# ASIC_2.net
KiCad netlist of a schematic drawn in Altium Designer
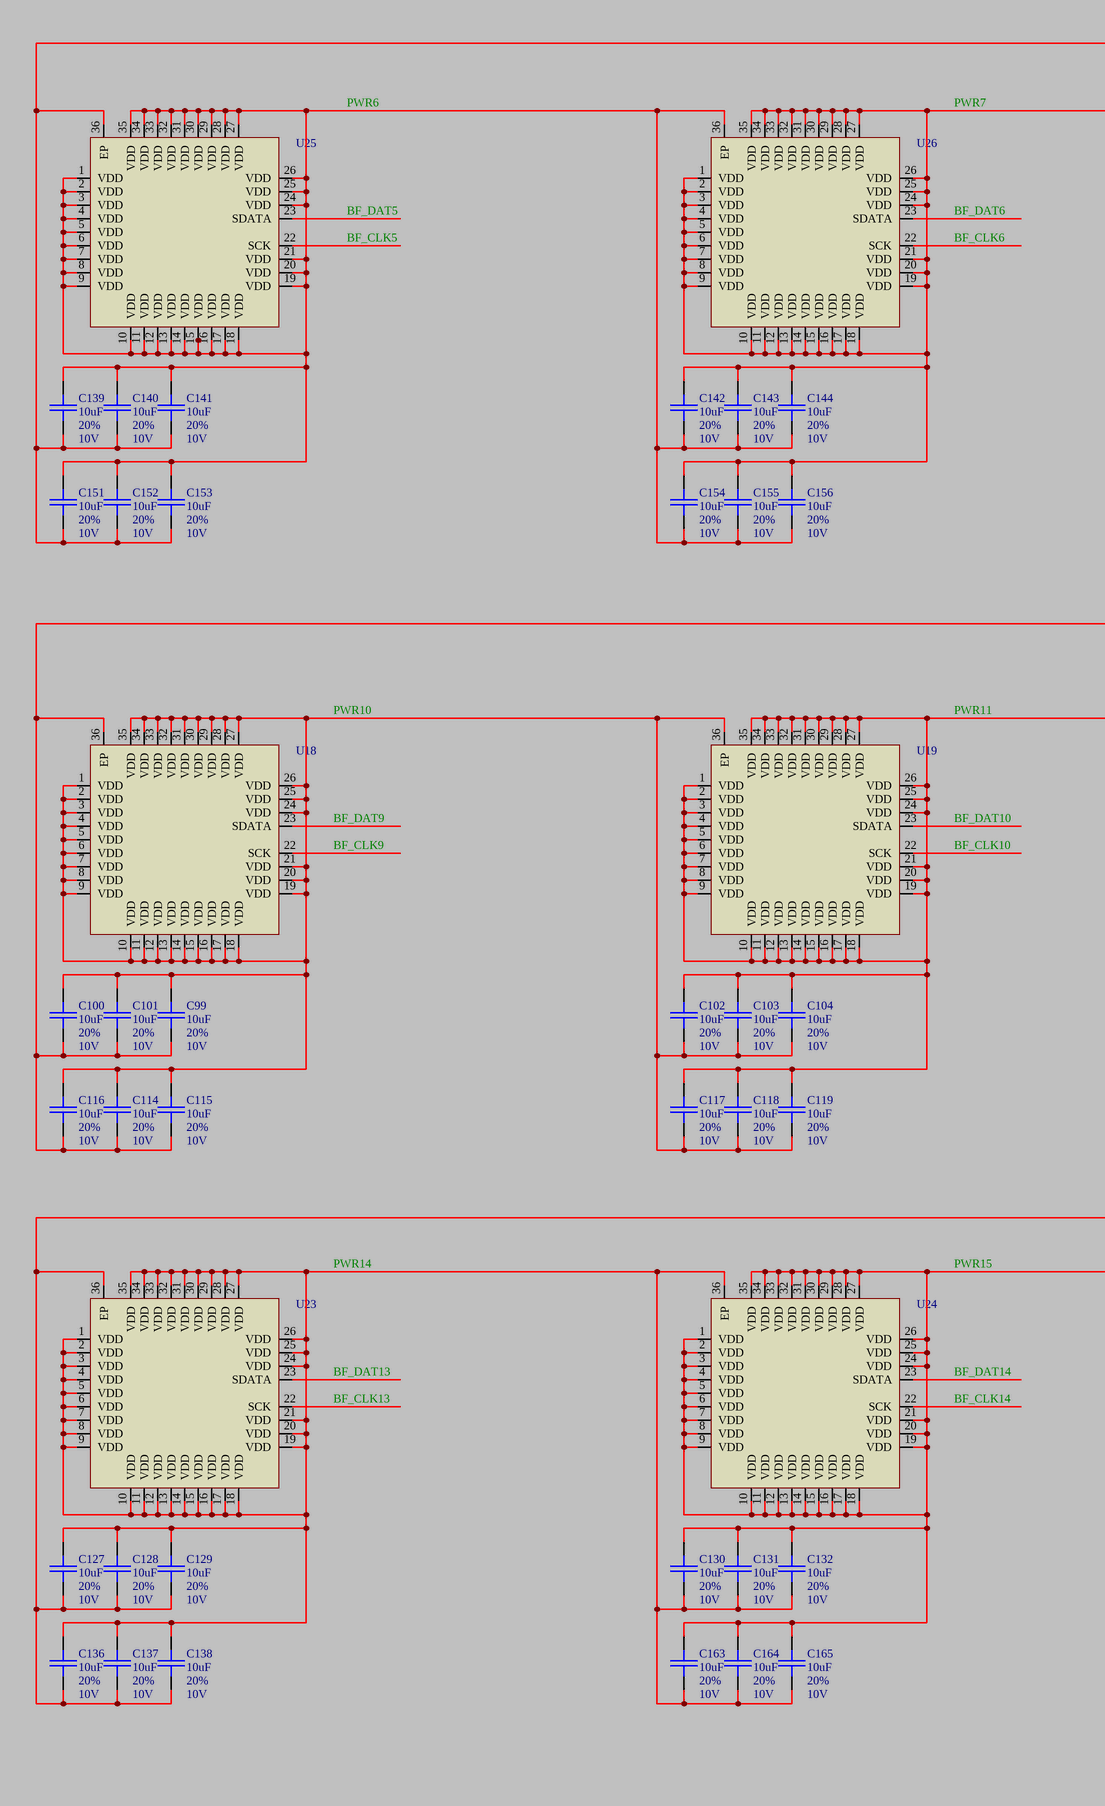
[diagram p0: ASIC_2.SchDoc, left]
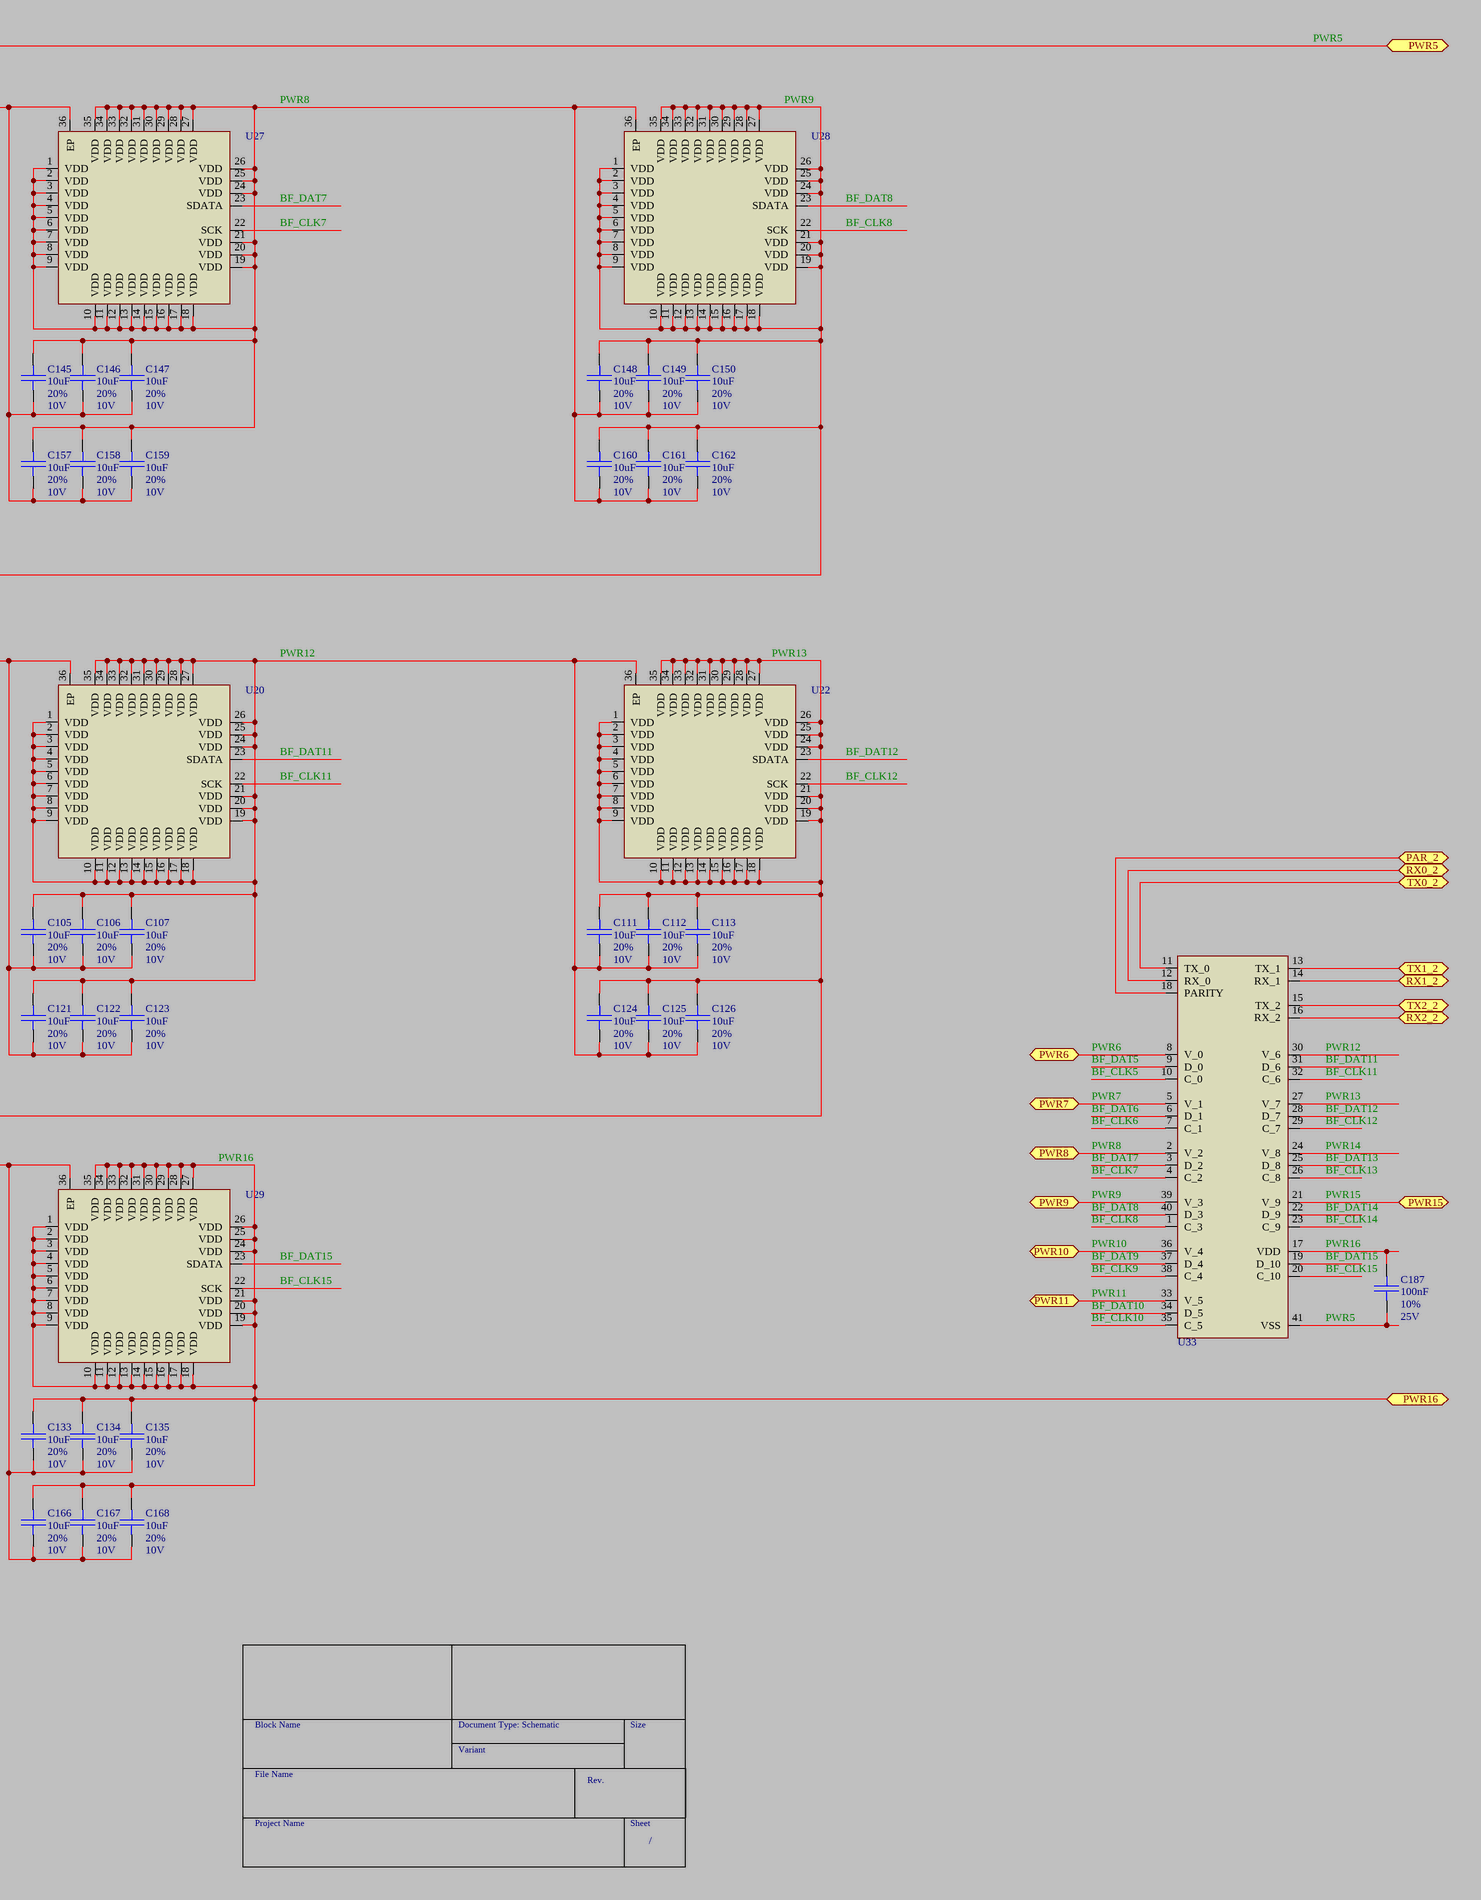
[diagram p1: ASIC_2.SchDoc, right]

(export (version "E")
  (design (tool "Eeschema 10.0.6"))
  (components
    (comp (ref "C99")
      (value "C")
      (footprint "SMD_0402_CAPC1005X70N")
      (fields
        (field (name "DB_PART_NUMBER") "CAP000047481")
        (field (name "DB_VALUE") "10uF")
        (field (name "DB_TOLERANCE") "20%")
        (field (name "DB_VOLTAGE") "10V")
        (field (name "DB_MANUFACTURER_PART") "SAMSUNG    CL05A106MP5NUNC")
        (field (name "DB_APPROVED_BY") "VSN")
      )
      (libsource (lib "Database_Libs1") (part "C"))
    )
    (comp (ref "C100")
      (value "C")
      (footprint "SMD_0402_CAPC1005X70N")
      (fields
        (field (name "DB_PART_NUMBER") "CAP000047481")
        (field (name "DB_VALUE") "10uF")
        (field (name "DB_TOLERANCE") "20%")
        (field (name "DB_VOLTAGE") "10V")
        (field (name "DB_MANUFACTURER_PART") "SAMSUNG    CL05A106MP5NUNC")
        (field (name "DB_APPROVED_BY") "VSN")
      )
      (libsource (lib "Database_Libs1") (part "C"))
    )
    (comp (ref "C101")
      (value "C")
      (footprint "SMD_0402_CAPC1005X70N")
      (fields
        (field (name "DB_PART_NUMBER") "CAP000047481")
        (field (name "DB_VALUE") "10uF")
        (field (name "DB_TOLERANCE") "20%")
        (field (name "DB_VOLTAGE") "10V")
        (field (name "DB_MANUFACTURER_PART") "SAMSUNG    CL05A106MP5NUNC")
        (field (name "DB_APPROVED_BY") "VSN")
      )
      (libsource (lib "Database_Libs1") (part "C"))
    )
    (comp (ref "C102")
      (value "C")
      (footprint "SMD_0402_CAPC1005X70N")
      (fields
        (field (name "DB_PART_NUMBER") "CAP000047481")
        (field (name "DB_VALUE") "10uF")
        (field (name "DB_TOLERANCE") "20%")
        (field (name "DB_VOLTAGE") "10V")
        (field (name "DB_MANUFACTURER_PART") "SAMSUNG    CL05A106MP5NUNC")
        (field (name "DB_APPROVED_BY") "VSN")
      )
      (libsource (lib "Database_Libs1") (part "C"))
    )
    (comp (ref "C103")
      (value "C")
      (footprint "SMD_0402_CAPC1005X70N")
      (fields
        (field (name "DB_PART_NUMBER") "CAP000047481")
        (field (name "DB_VALUE") "10uF")
        (field (name "DB_TOLERANCE") "20%")
        (field (name "DB_VOLTAGE") "10V")
        (field (name "DB_MANUFACTURER_PART") "SAMSUNG    CL05A106MP5NUNC")
        (field (name "DB_APPROVED_BY") "VSN")
      )
      (libsource (lib "Database_Libs1") (part "C"))
    )
    (comp (ref "C104")
      (value "C")
      (footprint "SMD_0402_CAPC1005X70N")
      (fields
        (field (name "DB_PART_NUMBER") "CAP000047481")
        (field (name "DB_VALUE") "10uF")
        (field (name "DB_TOLERANCE") "20%")
        (field (name "DB_VOLTAGE") "10V")
        (field (name "DB_MANUFACTURER_PART") "SAMSUNG    CL05A106MP5NUNC")
        (field (name "DB_APPROVED_BY") "VSN")
      )
      (libsource (lib "Database_Libs1") (part "C"))
    )
    (comp (ref "C105")
      (value "C")
      (footprint "SMD_0402_CAPC1005X70N")
      (fields
        (field (name "DB_PART_NUMBER") "CAP000047481")
        (field (name "DB_VALUE") "10uF")
        (field (name "DB_TOLERANCE") "20%")
        (field (name "DB_VOLTAGE") "10V")
        (field (name "DB_MANUFACTURER_PART") "SAMSUNG    CL05A106MP5NUNC")
        (field (name "DB_APPROVED_BY") "VSN")
      )
      (libsource (lib "Database_Libs1") (part "C"))
    )
    (comp (ref "C106")
      (value "C")
      (footprint "SMD_0402_CAPC1005X70N")
      (fields
        (field (name "DB_PART_NUMBER") "CAP000047481")
        (field (name "DB_VALUE") "10uF")
        (field (name "DB_TOLERANCE") "20%")
        (field (name "DB_VOLTAGE") "10V")
        (field (name "DB_MANUFACTURER_PART") "SAMSUNG    CL05A106MP5NUNC")
        (field (name "DB_APPROVED_BY") "VSN")
      )
      (libsource (lib "Database_Libs1") (part "C"))
    )
    (comp (ref "C107")
      (value "C")
      (footprint "SMD_0402_CAPC1005X70N")
      (fields
        (field (name "DB_PART_NUMBER") "CAP000047481")
        (field (name "DB_VALUE") "10uF")
        (field (name "DB_TOLERANCE") "20%")
        (field (name "DB_VOLTAGE") "10V")
        (field (name "DB_MANUFACTURER_PART") "SAMSUNG    CL05A106MP5NUNC")
        (field (name "DB_APPROVED_BY") "VSN")
      )
      (libsource (lib "Database_Libs1") (part "C"))
    )
    (comp (ref "C111")
      (value "C")
      (footprint "SMD_0402_CAPC1005X70N")
      (fields
        (field (name "DB_PART_NUMBER") "CAP000047481")
        (field (name "DB_VALUE") "10uF")
        (field (name "DB_TOLERANCE") "20%")
        (field (name "DB_VOLTAGE") "10V")
        (field (name "DB_MANUFACTURER_PART") "SAMSUNG    CL05A106MP5NUNC")
        (field (name "DB_APPROVED_BY") "VSN")
      )
      (libsource (lib "Database_Libs1") (part "C"))
    )
    (comp (ref "C112")
      (value "C")
      (footprint "SMD_0402_CAPC1005X70N")
      (fields
        (field (name "DB_PART_NUMBER") "CAP000047481")
        (field (name "DB_VALUE") "10uF")
        (field (name "DB_TOLERANCE") "20%")
        (field (name "DB_VOLTAGE") "10V")
        (field (name "DB_MANUFACTURER_PART") "SAMSUNG    CL05A106MP5NUNC")
        (field (name "DB_APPROVED_BY") "VSN")
      )
      (libsource (lib "Database_Libs1") (part "C"))
    )
    (comp (ref "C113")
      (value "C")
      (footprint "SMD_0402_CAPC1005X70N")
      (fields
        (field (name "DB_PART_NUMBER") "CAP000047481")
        (field (name "DB_VALUE") "10uF")
        (field (name "DB_TOLERANCE") "20%")
        (field (name "DB_VOLTAGE") "10V")
        (field (name "DB_MANUFACTURER_PART") "SAMSUNG    CL05A106MP5NUNC")
        (field (name "DB_APPROVED_BY") "VSN")
      )
      (libsource (lib "Database_Libs1") (part "C"))
    )
    (comp (ref "C114")
      (value "C")
      (footprint "SMD_0402_CAPC1005X70N")
      (fields
        (field (name "DB_PART_NUMBER") "CAP000047481")
        (field (name "DB_VALUE") "10uF")
        (field (name "DB_TOLERANCE") "20%")
        (field (name "DB_VOLTAGE") "10V")
        (field (name "DB_MANUFACTURER_PART") "SAMSUNG    CL05A106MP5NUNC")
        (field (name "DB_APPROVED_BY") "VSN")
      )
      (libsource (lib "Database_Libs1") (part "C"))
    )
    (comp (ref "C115")
      (value "C")
      (footprint "SMD_0402_CAPC1005X70N")
      (fields
        (field (name "DB_PART_NUMBER") "CAP000047481")
        (field (name "DB_VALUE") "10uF")
        (field (name "DB_TOLERANCE") "20%")
        (field (name "DB_VOLTAGE") "10V")
        (field (name "DB_MANUFACTURER_PART") "SAMSUNG    CL05A106MP5NUNC")
        (field (name "DB_APPROVED_BY") "VSN")
      )
      (libsource (lib "Database_Libs1") (part "C"))
    )
    (comp (ref "C116")
      (value "C")
      (footprint "SMD_0402_CAPC1005X70N")
      (fields
        (field (name "DB_PART_NUMBER") "CAP000047481")
        (field (name "DB_VALUE") "10uF")
        (field (name "DB_TOLERANCE") "20%")
        (field (name "DB_VOLTAGE") "10V")
        (field (name "DB_MANUFACTURER_PART") "SAMSUNG    CL05A106MP5NUNC")
        (field (name "DB_APPROVED_BY") "VSN")
      )
      (libsource (lib "Database_Libs1") (part "C"))
    )
    (comp (ref "C117")
      (value "C")
      (footprint "SMD_0402_CAPC1005X70N")
      (fields
        (field (name "DB_PART_NUMBER") "CAP000047481")
        (field (name "DB_VALUE") "10uF")
        (field (name "DB_TOLERANCE") "20%")
        (field (name "DB_VOLTAGE") "10V")
        (field (name "DB_MANUFACTURER_PART") "SAMSUNG    CL05A106MP5NUNC")
        (field (name "DB_APPROVED_BY") "VSN")
      )
      (libsource (lib "Database_Libs1") (part "C"))
    )
    (comp (ref "C118")
      (value "C")
      (footprint "SMD_0402_CAPC1005X70N")
      (fields
        (field (name "DB_PART_NUMBER") "CAP000047481")
        (field (name "DB_VALUE") "10uF")
        (field (name "DB_TOLERANCE") "20%")
        (field (name "DB_VOLTAGE") "10V")
        (field (name "DB_MANUFACTURER_PART") "SAMSUNG    CL05A106MP5NUNC")
        (field (name "DB_APPROVED_BY") "VSN")
      )
      (libsource (lib "Database_Libs1") (part "C"))
    )
    (comp (ref "C119")
      (value "C")
      (footprint "SMD_0402_CAPC1005X70N")
      (fields
        (field (name "DB_PART_NUMBER") "CAP000047481")
        (field (name "DB_VALUE") "10uF")
        (field (name "DB_TOLERANCE") "20%")
        (field (name "DB_VOLTAGE") "10V")
        (field (name "DB_MANUFACTURER_PART") "SAMSUNG    CL05A106MP5NUNC")
        (field (name "DB_APPROVED_BY") "VSN")
      )
      (libsource (lib "Database_Libs1") (part "C"))
    )
    (comp (ref "C121")
      (value "C")
      (footprint "SMD_0402_CAPC1005X70N")
      (fields
        (field (name "DB_PART_NUMBER") "CAP000047481")
        (field (name "DB_VALUE") "10uF")
        (field (name "DB_TOLERANCE") "20%")
        (field (name "DB_VOLTAGE") "10V")
        (field (name "DB_MANUFACTURER_PART") "SAMSUNG    CL05A106MP5NUNC")
        (field (name "DB_APPROVED_BY") "VSN")
      )
      (libsource (lib "Database_Libs1") (part "C"))
    )
    (comp (ref "C122")
      (value "C")
      (footprint "SMD_0402_CAPC1005X70N")
      (fields
        (field (name "DB_PART_NUMBER") "CAP000047481")
        (field (name "DB_VALUE") "10uF")
        (field (name "DB_TOLERANCE") "20%")
        (field (name "DB_VOLTAGE") "10V")
        (field (name "DB_MANUFACTURER_PART") "SAMSUNG    CL05A106MP5NUNC")
        (field (name "DB_APPROVED_BY") "VSN")
      )
      (libsource (lib "Database_Libs1") (part "C"))
    )
    (comp (ref "C123")
      (value "C")
      (footprint "SMD_0402_CAPC1005X70N")
      (fields
        (field (name "DB_PART_NUMBER") "CAP000047481")
        (field (name "DB_VALUE") "10uF")
        (field (name "DB_TOLERANCE") "20%")
        (field (name "DB_VOLTAGE") "10V")
        (field (name "DB_MANUFACTURER_PART") "SAMSUNG    CL05A106MP5NUNC")
        (field (name "DB_APPROVED_BY") "VSN")
      )
      (libsource (lib "Database_Libs1") (part "C"))
    )
    (comp (ref "C124")
      (value "C")
      (footprint "SMD_0402_CAPC1005X70N")
      (fields
        (field (name "DB_PART_NUMBER") "CAP000047481")
        (field (name "DB_VALUE") "10uF")
        (field (name "DB_TOLERANCE") "20%")
        (field (name "DB_VOLTAGE") "10V")
        (field (name "DB_MANUFACTURER_PART") "SAMSUNG    CL05A106MP5NUNC")
        (field (name "DB_APPROVED_BY") "VSN")
      )
      (libsource (lib "Database_Libs1") (part "C"))
    )
    (comp (ref "C125")
      (value "C")
      (footprint "SMD_0402_CAPC1005X70N")
      (fields
        (field (name "DB_PART_NUMBER") "CAP000047481")
        (field (name "DB_VALUE") "10uF")
        (field (name "DB_TOLERANCE") "20%")
        (field (name "DB_VOLTAGE") "10V")
        (field (name "DB_MANUFACTURER_PART") "SAMSUNG    CL05A106MP5NUNC")
        (field (name "DB_APPROVED_BY") "VSN")
      )
      (libsource (lib "Database_Libs1") (part "C"))
    )
    (comp (ref "C126")
      (value "C")
      (footprint "SMD_0402_CAPC1005X70N")
      (fields
        (field (name "DB_PART_NUMBER") "CAP000047481")
        (field (name "DB_VALUE") "10uF")
        (field (name "DB_TOLERANCE") "20%")
        (field (name "DB_VOLTAGE") "10V")
        (field (name "DB_MANUFACTURER_PART") "SAMSUNG    CL05A106MP5NUNC")
        (field (name "DB_APPROVED_BY") "VSN")
      )
      (libsource (lib "Database_Libs1") (part "C"))
    )
    (comp (ref "C127")
      (value "C")
      (footprint "SMD_0402_CAPC1005X70N")
      (fields
        (field (name "DB_PART_NUMBER") "CAP000047481")
        (field (name "DB_VALUE") "10uF")
        (field (name "DB_TOLERANCE") "20%")
        (field (name "DB_VOLTAGE") "10V")
        (field (name "DB_MANUFACTURER_PART") "SAMSUNG    CL05A106MP5NUNC")
        (field (name "DB_APPROVED_BY") "VSN")
      )
      (libsource (lib "Database_Libs1") (part "C"))
    )
    (comp (ref "C128")
      (value "C")
      (footprint "SMD_0402_CAPC1005X70N")
      (fields
        (field (name "DB_PART_NUMBER") "CAP000047481")
        (field (name "DB_VALUE") "10uF")
        (field (name "DB_TOLERANCE") "20%")
        (field (name "DB_VOLTAGE") "10V")
        (field (name "DB_MANUFACTURER_PART") "SAMSUNG    CL05A106MP5NUNC")
        (field (name "DB_APPROVED_BY") "VSN")
      )
      (libsource (lib "Database_Libs1") (part "C"))
    )
    (comp (ref "C129")
      (value "C")
      (footprint "SMD_0402_CAPC1005X70N")
      (fields
        (field (name "DB_PART_NUMBER") "CAP000047481")
        (field (name "DB_VALUE") "10uF")
        (field (name "DB_TOLERANCE") "20%")
        (field (name "DB_VOLTAGE") "10V")
        (field (name "DB_MANUFACTURER_PART") "SAMSUNG    CL05A106MP5NUNC")
        (field (name "DB_APPROVED_BY") "VSN")
      )
      (libsource (lib "Database_Libs1") (part "C"))
    )
    (comp (ref "C130")
      (value "C")
      (footprint "SMD_0402_CAPC1005X70N")
      (fields
        (field (name "DB_PART_NUMBER") "CAP000047481")
        (field (name "DB_VALUE") "10uF")
        (field (name "DB_TOLERANCE") "20%")
        (field (name "DB_VOLTAGE") "10V")
        (field (name "DB_MANUFACTURER_PART") "SAMSUNG    CL05A106MP5NUNC")
        (field (name "DB_APPROVED_BY") "VSN")
      )
      (libsource (lib "Database_Libs1") (part "C"))
    )
    (comp (ref "C131")
      (value "C")
      (footprint "SMD_0402_CAPC1005X70N")
      (fields
        (field (name "DB_PART_NUMBER") "CAP000047481")
        (field (name "DB_VALUE") "10uF")
        (field (name "DB_TOLERANCE") "20%")
        (field (name "DB_VOLTAGE") "10V")
        (field (name "DB_MANUFACTURER_PART") "SAMSUNG    CL05A106MP5NUNC")
        (field (name "DB_APPROVED_BY") "VSN")
      )
      (libsource (lib "Database_Libs1") (part "C"))
    )
    (comp (ref "C132")
      (value "C")
      (footprint "SMD_0402_CAPC1005X70N")
      (fields
        (field (name "DB_PART_NUMBER") "CAP000047481")
        (field (name "DB_VALUE") "10uF")
        (field (name "DB_TOLERANCE") "20%")
        (field (name "DB_VOLTAGE") "10V")
        (field (name "DB_MANUFACTURER_PART") "SAMSUNG    CL05A106MP5NUNC")
        (field (name "DB_APPROVED_BY") "VSN")
      )
      (libsource (lib "Database_Libs1") (part "C"))
    )
    (comp (ref "C133")
      (value "C")
      (footprint "SMD_0402_CAPC1005X70N")
      (fields
        (field (name "DB_PART_NUMBER") "CAP000047481")
        (field (name "DB_VALUE") "10uF")
        (field (name "DB_TOLERANCE") "20%")
        (field (name "DB_VOLTAGE") "10V")
        (field (name "DB_MANUFACTURER_PART") "SAMSUNG    CL05A106MP5NUNC")
        (field (name "DB_APPROVED_BY") "VSN")
      )
      (libsource (lib "Database_Libs1") (part "C"))
    )
    (comp (ref "C134")
      (value "C")
      (footprint "SMD_0402_CAPC1005X70N")
      (fields
        (field (name "DB_PART_NUMBER") "CAP000047481")
        (field (name "DB_VALUE") "10uF")
        (field (name "DB_TOLERANCE") "20%")
        (field (name "DB_VOLTAGE") "10V")
        (field (name "DB_MANUFACTURER_PART") "SAMSUNG    CL05A106MP5NUNC")
        (field (name "DB_APPROVED_BY") "VSN")
      )
      (libsource (lib "Database_Libs1") (part "C"))
    )
    (comp (ref "C135")
      (value "C")
      (footprint "SMD_0402_CAPC1005X70N")
      (fields
        (field (name "DB_PART_NUMBER") "CAP000047481")
        (field (name "DB_VALUE") "10uF")
        (field (name "DB_TOLERANCE") "20%")
        (field (name "DB_VOLTAGE") "10V")
        (field (name "DB_MANUFACTURER_PART") "SAMSUNG    CL05A106MP5NUNC")
        (field (name "DB_APPROVED_BY") "VSN")
      )
      (libsource (lib "Database_Libs1") (part "C"))
    )
    (comp (ref "C136")
      (value "C")
      (footprint "SMD_0402_CAPC1005X70N")
      (fields
        (field (name "DB_PART_NUMBER") "CAP000047481")
        (field (name "DB_VALUE") "10uF")
        (field (name "DB_TOLERANCE") "20%")
        (field (name "DB_VOLTAGE") "10V")
        (field (name "DB_MANUFACTURER_PART") "SAMSUNG    CL05A106MP5NUNC")
        (field (name "DB_APPROVED_BY") "VSN")
      )
      (libsource (lib "Database_Libs1") (part "C"))
    )
    (comp (ref "C137")
      (value "C")
      (footprint "SMD_0402_CAPC1005X70N")
      (fields
        (field (name "DB_PART_NUMBER") "CAP000047481")
        (field (name "DB_VALUE") "10uF")
        (field (name "DB_TOLERANCE") "20%")
        (field (name "DB_VOLTAGE") "10V")
        (field (name "DB_MANUFACTURER_PART") "SAMSUNG    CL05A106MP5NUNC")
        (field (name "DB_APPROVED_BY") "VSN")
      )
      (libsource (lib "Database_Libs1") (part "C"))
    )
    (comp (ref "C138")
      (value "C")
      (footprint "SMD_0402_CAPC1005X70N")
      (fields
        (field (name "DB_PART_NUMBER") "CAP000047481")
        (field (name "DB_VALUE") "10uF")
        (field (name "DB_TOLERANCE") "20%")
        (field (name "DB_VOLTAGE") "10V")
        (field (name "DB_MANUFACTURER_PART") "SAMSUNG    CL05A106MP5NUNC")
        (field (name "DB_APPROVED_BY") "VSN")
      )
      (libsource (lib "Database_Libs1") (part "C"))
    )
    (comp (ref "C139")
      (value "C")
      (footprint "SMD_0402_CAPC1005X70N")
      (fields
        (field (name "DB_PART_NUMBER") "CAP000047481")
        (field (name "DB_VALUE") "10uF")
        (field (name "DB_TOLERANCE") "20%")
        (field (name "DB_VOLTAGE") "10V")
        (field (name "DB_MANUFACTURER_PART") "SAMSUNG    CL05A106MP5NUNC")
        (field (name "DB_APPROVED_BY") "VSN")
      )
      (libsource (lib "Database_Libs1") (part "C"))
    )
    (comp (ref "C140")
      (value "C")
      (footprint "SMD_0402_CAPC1005X70N")
      (fields
        (field (name "DB_PART_NUMBER") "CAP000047481")
        (field (name "DB_VALUE") "10uF")
        (field (name "DB_TOLERANCE") "20%")
        (field (name "DB_VOLTAGE") "10V")
        (field (name "DB_MANUFACTURER_PART") "SAMSUNG    CL05A106MP5NUNC")
        (field (name "DB_APPROVED_BY") "VSN")
      )
      (libsource (lib "Database_Libs1") (part "C"))
    )
    (comp (ref "C141")
      (value "C")
      (footprint "SMD_0402_CAPC1005X70N")
      (fields
        (field (name "DB_PART_NUMBER") "CAP000047481")
        (field (name "DB_VALUE") "10uF")
        (field (name "DB_TOLERANCE") "20%")
        (field (name "DB_VOLTAGE") "10V")
        (field (name "DB_MANUFACTURER_PART") "SAMSUNG    CL05A106MP5NUNC")
        (field (name "DB_APPROVED_BY") "VSN")
      )
      (libsource (lib "Database_Libs1") (part "C"))
    )
    (comp (ref "C142")
      (value "C")
      (footprint "SMD_0402_CAPC1005X70N")
      (fields
        (field (name "DB_PART_NUMBER") "CAP000047481")
        (field (name "DB_VALUE") "10uF")
        (field (name "DB_TOLERANCE") "20%")
        (field (name "DB_VOLTAGE") "10V")
        (field (name "DB_MANUFACTURER_PART") "SAMSUNG    CL05A106MP5NUNC")
        (field (name "DB_APPROVED_BY") "VSN")
      )
      (libsource (lib "Database_Libs1") (part "C"))
    )
    (comp (ref "C143")
      (value "C")
      (footprint "SMD_0402_CAPC1005X70N")
      (fields
        (field (name "DB_PART_NUMBER") "CAP000047481")
        (field (name "DB_VALUE") "10uF")
        (field (name "DB_TOLERANCE") "20%")
        (field (name "DB_VOLTAGE") "10V")
        (field (name "DB_MANUFACTURER_PART") "SAMSUNG    CL05A106MP5NUNC")
        (field (name "DB_APPROVED_BY") "VSN")
      )
      (libsource (lib "Database_Libs1") (part "C"))
    )
    (comp (ref "C144")
      (value "C")
      (footprint "SMD_0402_CAPC1005X70N")
      (fields
        (field (name "DB_PART_NUMBER") "CAP000047481")
        (field (name "DB_VALUE") "10uF")
        (field (name "DB_TOLERANCE") "20%")
        (field (name "DB_VOLTAGE") "10V")
        (field (name "DB_MANUFACTURER_PART") "SAMSUNG    CL05A106MP5NUNC")
        (field (name "DB_APPROVED_BY") "VSN")
      )
      (libsource (lib "Database_Libs1") (part "C"))
    )
    (comp (ref "C145")
      (value "C")
      (footprint "SMD_0402_CAPC1005X70N")
      (fields
        (field (name "DB_PART_NUMBER") "CAP000047481")
        (field (name "DB_VALUE") "10uF")
        (field (name "DB_TOLERANCE") "20%")
        (field (name "DB_VOLTAGE") "10V")
        (field (name "DB_MANUFACTURER_PART") "SAMSUNG    CL05A106MP5NUNC")
        (field (name "DB_APPROVED_BY") "VSN")
      )
      (libsource (lib "Database_Libs1") (part "C"))
    )
    (comp (ref "C146")
      (value "C")
      (footprint "SMD_0402_CAPC1005X70N")
      (fields
        (field (name "DB_PART_NUMBER") "CAP000047481")
        (field (name "DB_VALUE") "10uF")
        (field (name "DB_TOLERANCE") "20%")
        (field (name "DB_VOLTAGE") "10V")
        (field (name "DB_MANUFACTURER_PART") "SAMSUNG    CL05A106MP5NUNC")
        (field (name "DB_APPROVED_BY") "VSN")
      )
      (libsource (lib "Database_Libs1") (part "C"))
    )
    (comp (ref "C147")
      (value "C")
      (footprint "SMD_0402_CAPC1005X70N")
      (fields
        (field (name "DB_PART_NUMBER") "CAP000047481")
        (field (name "DB_VALUE") "10uF")
        (field (name "DB_TOLERANCE") "20%")
        (field (name "DB_VOLTAGE") "10V")
        (field (name "DB_MANUFACTURER_PART") "SAMSUNG    CL05A106MP5NUNC")
        (field (name "DB_APPROVED_BY") "VSN")
      )
      (libsource (lib "Database_Libs1") (part "C"))
    )
    (comp (ref "C148")
      (value "C")
      (footprint "SMD_0402_CAPC1005X70N")
      (fields
        (field (name "DB_PART_NUMBER") "CAP000047481")
        (field (name "DB_VALUE") "10uF")
        (field (name "DB_TOLERANCE") "20%")
        (field (name "DB_VOLTAGE") "10V")
        (field (name "DB_MANUFACTURER_PART") "SAMSUNG    CL05A106MP5NUNC")
        (field (name "DB_APPROVED_BY") "VSN")
      )
      (libsource (lib "Database_Libs1") (part "C"))
    )
    (comp (ref "C149")
      (value "C")
      (footprint "SMD_0402_CAPC1005X70N")
      (fields
        (field (name "DB_PART_NUMBER") "CAP000047481")
        (field (name "DB_VALUE") "10uF")
        (field (name "DB_TOLERANCE") "20%")
        (field (name "DB_VOLTAGE") "10V")
        (field (name "DB_MANUFACTURER_PART") "SAMSUNG    CL05A106MP5NUNC")
        (field (name "DB_APPROVED_BY") "VSN")
      )
      (libsource (lib "Database_Libs1") (part "C"))
    )
    (comp (ref "C150")
      (value "C")
      (footprint "SMD_0402_CAPC1005X70N")
      (fields
        (field (name "DB_PART_NUMBER") "CAP000047481")
        (field (name "DB_VALUE") "10uF")
        (field (name "DB_TOLERANCE") "20%")
        (field (name "DB_VOLTAGE") "10V")
        (field (name "DB_MANUFACTURER_PART") "SAMSUNG    CL05A106MP5NUNC")
        (field (name "DB_APPROVED_BY") "VSN")
      )
      (libsource (lib "Database_Libs1") (part "C"))
    )
    (comp (ref "C151")
      (value "C")
      (footprint "SMD_0402_CAPC1005X70N")
      (fields
        (field (name "DB_PART_NUMBER") "CAP000047481")
        (field (name "DB_VALUE") "10uF")
        (field (name "DB_TOLERANCE") "20%")
        (field (name "DB_VOLTAGE") "10V")
        (field (name "DB_MANUFACTURER_PART") "SAMSUNG    CL05A106MP5NUNC")
        (field (name "DB_APPROVED_BY") "VSN")
      )
      (libsource (lib "Database_Libs1") (part "C"))
    )
    (comp (ref "C152")
      (value "C")
      (footprint "SMD_0402_CAPC1005X70N")
      (fields
        (field (name "DB_PART_NUMBER") "CAP000047481")
        (field (name "DB_VALUE") "10uF")
        (field (name "DB_TOLERANCE") "20%")
        (field (name "DB_VOLTAGE") "10V")
        (field (name "DB_MANUFACTURER_PART") "SAMSUNG    CL05A106MP5NUNC")
        (field (name "DB_APPROVED_BY") "VSN")
      )
      (libsource (lib "Database_Libs1") (part "C"))
    )
    (comp (ref "C153")
      (value "C")
      (footprint "SMD_0402_CAPC1005X70N")
      (fields
        (field (name "DB_PART_NUMBER") "CAP000047481")
        (field (name "DB_VALUE") "10uF")
        (field (name "DB_TOLERANCE") "20%")
        (field (name "DB_VOLTAGE") "10V")
        (field (name "DB_MANUFACTURER_PART") "SAMSUNG    CL05A106MP5NUNC")
        (field (name "DB_APPROVED_BY") "VSN")
      )
      (libsource (lib "Database_Libs1") (part "C"))
    )
    (comp (ref "C154")
      (value "C")
      (footprint "SMD_0402_CAPC1005X70N")
      (fields
        (field (name "DB_PART_NUMBER") "CAP000047481")
        (field (name "DB_VALUE") "10uF")
        (field (name "DB_TOLERANCE") "20%")
        (field (name "DB_VOLTAGE") "10V")
        (field (name "DB_MANUFACTURER_PART") "SAMSUNG    CL05A106MP5NUNC")
        (field (name "DB_APPROVED_BY") "VSN")
      )
      (libsource (lib "Database_Libs1") (part "C"))
    )
    (comp (ref "C155")
      (value "C")
      (footprint "SMD_0402_CAPC1005X70N")
      (fields
        (field (name "DB_PART_NUMBER") "CAP000047481")
        (field (name "DB_VALUE") "10uF")
        (field (name "DB_TOLERANCE") "20%")
        (field (name "DB_VOLTAGE") "10V")
        (field (name "DB_MANUFACTURER_PART") "SAMSUNG    CL05A106MP5NUNC")
        (field (name "DB_APPROVED_BY") "VSN")
      )
      (libsource (lib "Database_Libs1") (part "C"))
    )
    (comp (ref "C156")
      (value "C")
      (footprint "SMD_0402_CAPC1005X70N")
      (fields
        (field (name "DB_PART_NUMBER") "CAP000047481")
        (field (name "DB_VALUE") "10uF")
        (field (name "DB_TOLERANCE") "20%")
        (field (name "DB_VOLTAGE") "10V")
        (field (name "DB_MANUFACTURER_PART") "SAMSUNG    CL05A106MP5NUNC")
        (field (name "DB_APPROVED_BY") "VSN")
      )
      (libsource (lib "Database_Libs1") (part "C"))
    )
    (comp (ref "C157")
      (value "C")
      (footprint "SMD_0402_CAPC1005X70N")
      (fields
        (field (name "DB_PART_NUMBER") "CAP000047481")
        (field (name "DB_VALUE") "10uF")
        (field (name "DB_TOLERANCE") "20%")
        (field (name "DB_VOLTAGE") "10V")
        (field (name "DB_MANUFACTURER_PART") "SAMSUNG    CL05A106MP5NUNC")
        (field (name "DB_APPROVED_BY") "VSN")
      )
      (libsource (lib "Database_Libs1") (part "C"))
    )
    (comp (ref "C158")
      (value "C")
      (footprint "SMD_0402_CAPC1005X70N")
      (fields
        (field (name "DB_PART_NUMBER") "CAP000047481")
        (field (name "DB_VALUE") "10uF")
        (field (name "DB_TOLERANCE") "20%")
        (field (name "DB_VOLTAGE") "10V")
        (field (name "DB_MANUFACTURER_PART") "SAMSUNG    CL05A106MP5NUNC")
        (field (name "DB_APPROVED_BY") "VSN")
      )
      (libsource (lib "Database_Libs1") (part "C"))
    )
    (comp (ref "C159")
      (value "C")
      (footprint "SMD_0402_CAPC1005X70N")
      (fields
        (field (name "DB_PART_NUMBER") "CAP000047481")
        (field (name "DB_VALUE") "10uF")
        (field (name "DB_TOLERANCE") "20%")
        (field (name "DB_VOLTAGE") "10V")
        (field (name "DB_MANUFACTURER_PART") "SAMSUNG    CL05A106MP5NUNC")
        (field (name "DB_APPROVED_BY") "VSN")
      )
      (libsource (lib "Database_Libs1") (part "C"))
    )
    (comp (ref "C160")
      (value "C")
      (footprint "SMD_0402_CAPC1005X70N")
      (fields
        (field (name "DB_PART_NUMBER") "CAP000047481")
        (field (name "DB_VALUE") "10uF")
        (field (name "DB_TOLERANCE") "20%")
        (field (name "DB_VOLTAGE") "10V")
        (field (name "DB_MANUFACTURER_PART") "SAMSUNG    CL05A106MP5NUNC")
        (field (name "DB_APPROVED_BY") "VSN")
      )
      (libsource (lib "Database_Libs1") (part "C"))
    )
    (comp (ref "C161")
      (value "C")
      (footprint "SMD_0402_CAPC1005X70N")
      (fields
        (field (name "DB_PART_NUMBER") "CAP000047481")
        (field (name "DB_VALUE") "10uF")
        (field (name "DB_TOLERANCE") "20%")
        (field (name "DB_VOLTAGE") "10V")
        (field (name "DB_MANUFACTURER_PART") "SAMSUNG    CL05A106MP5NUNC")
        (field (name "DB_APPROVED_BY") "VSN")
      )
      (libsource (lib "Database_Libs1") (part "C"))
    )
    (comp (ref "C162")
      (value "C")
      (footprint "SMD_0402_CAPC1005X70N")
      (fields
        (field (name "DB_PART_NUMBER") "CAP000047481")
        (field (name "DB_VALUE") "10uF")
        (field (name "DB_TOLERANCE") "20%")
        (field (name "DB_VOLTAGE") "10V")
        (field (name "DB_MANUFACTURER_PART") "SAMSUNG    CL05A106MP5NUNC")
        (field (name "DB_APPROVED_BY") "VSN")
      )
      (libsource (lib "Database_Libs1") (part "C"))
    )
    (comp (ref "C163")
      (value "C")
      (footprint "SMD_0402_CAPC1005X70N")
      (fields
        (field (name "DB_PART_NUMBER") "CAP000047481")
        (field (name "DB_VALUE") "10uF")
        (field (name "DB_TOLERANCE") "20%")
        (field (name "DB_VOLTAGE") "10V")
        (field (name "DB_MANUFACTURER_PART") "SAMSUNG    CL05A106MP5NUNC")
        (field (name "DB_APPROVED_BY") "VSN")
      )
      (libsource (lib "Database_Libs1") (part "C"))
    )
    (comp (ref "C164")
      (value "C")
      (footprint "SMD_0402_CAPC1005X70N")
      (fields
        (field (name "DB_PART_NUMBER") "CAP000047481")
        (field (name "DB_VALUE") "10uF")
        (field (name "DB_TOLERANCE") "20%")
        (field (name "DB_VOLTAGE") "10V")
        (field (name "DB_MANUFACTURER_PART") "SAMSUNG    CL05A106MP5NUNC")
        (field (name "DB_APPROVED_BY") "VSN")
      )
      (libsource (lib "Database_Libs1") (part "C"))
    )
    (comp (ref "C165")
      (value "C")
      (footprint "SMD_0402_CAPC1005X70N")
      (fields
        (field (name "DB_PART_NUMBER") "CAP000047481")
        (field (name "DB_VALUE") "10uF")
        (field (name "DB_TOLERANCE") "20%")
        (field (name "DB_VOLTAGE") "10V")
        (field (name "DB_MANUFACTURER_PART") "SAMSUNG    CL05A106MP5NUNC")
        (field (name "DB_APPROVED_BY") "VSN")
      )
      (libsource (lib "Database_Libs1") (part "C"))
    )
    (comp (ref "C166")
      (value "C")
      (footprint "SMD_0402_CAPC1005X70N")
      (fields
        (field (name "DB_PART_NUMBER") "CAP000047481")
        (field (name "DB_VALUE") "10uF")
        (field (name "DB_TOLERANCE") "20%")
        (field (name "DB_VOLTAGE") "10V")
        (field (name "DB_MANUFACTURER_PART") "SAMSUNG    CL05A106MP5NUNC")
        (field (name "DB_APPROVED_BY") "VSN")
      )
      (libsource (lib "Database_Libs1") (part "C"))
    )
    (comp (ref "C167")
      (value "C")
      (footprint "SMD_0402_CAPC1005X70N")
      (fields
        (field (name "DB_PART_NUMBER") "CAP000047481")
        (field (name "DB_VALUE") "10uF")
        (field (name "DB_TOLERANCE") "20%")
        (field (name "DB_VOLTAGE") "10V")
        (field (name "DB_MANUFACTURER_PART") "SAMSUNG    CL05A106MP5NUNC")
        (field (name "DB_APPROVED_BY") "VSN")
      )
      (libsource (lib "Database_Libs1") (part "C"))
    )
    (comp (ref "C168")
      (value "C")
      (footprint "SMD_0402_CAPC1005X70N")
      (fields
        (field (name "DB_PART_NUMBER") "CAP000047481")
        (field (name "DB_VALUE") "10uF")
        (field (name "DB_TOLERANCE") "20%")
        (field (name "DB_VOLTAGE") "10V")
        (field (name "DB_MANUFACTURER_PART") "SAMSUNG    CL05A106MP5NUNC")
        (field (name "DB_APPROVED_BY") "VSN")
      )
      (libsource (lib "Database_Libs1") (part "C"))
    )
    (comp (ref "C187")
      (value "C")
      (footprint "SMD_0402_CAPC1005X55N")
      (fields
        (field (name "DB_PART_NUMBER") "CAP000047469")
        (field (name "DB_VALUE") "100nF")
        (field (name "DB_TOLERANCE") "10%")
        (field (name "DB_VOLTAGE") "25V")
        (field (name "DB_MANUFACTURER_PART") "SAMSUNG    CL05A104KA5NNNC")
        (field (name "DB_APPROVED_BY") "VSN")
      )
      (libsource (lib "Database_Libs1") (part "C"))
    )
    (comp (ref "U18")
      (value "IC_BITFURY16")
      (footprint "SMD_QFN50P600X600X175-36AN")
      (description "BitFury 2016 16 nm")
      (libsource (lib "BitCoin") (part "IC_BITFURY16"))
    )
    (comp (ref "U19")
      (value "IC_BITFURY16")
      (footprint "SMD_QFN50P600X600X175-36AN")
      (description "BitFury 2016 16 nm")
      (libsource (lib "BitCoin") (part "IC_BITFURY16"))
    )
    (comp (ref "U20")
      (value "IC_BITFURY16")
      (footprint "SMD_QFN50P600X600X175-36AN")
      (description "BitFury 2016 16 nm")
      (libsource (lib "BitCoin") (part "IC_BITFURY16"))
    )
    (comp (ref "U22")
      (value "IC_BITFURY16")
      (footprint "SMD_QFN50P600X600X175-36AN")
      (description "BitFury 2016 16 nm")
      (libsource (lib "BitCoin") (part "IC_BITFURY16"))
    )
    (comp (ref "U23")
      (value "IC_BITFURY16")
      (footprint "SMD_QFN50P600X600X175-36AN")
      (description "BitFury 2016 16 nm")
      (libsource (lib "BitCoin") (part "IC_BITFURY16"))
    )
    (comp (ref "U24")
      (value "IC_BITFURY16")
      (footprint "SMD_QFN50P600X600X175-36AN")
      (description "BitFury 2016 16 nm")
      (libsource (lib "BitCoin") (part "IC_BITFURY16"))
    )
    (comp (ref "U25")
      (value "IC_BITFURY16")
      (footprint "SMD_QFN50P600X600X175-36AN")
      (description "BitFury 2016 16 nm")
      (libsource (lib "BitCoin") (part "IC_BITFURY16"))
    )
    (comp (ref "U26")
      (value "IC_BITFURY16")
      (footprint "SMD_QFN50P600X600X175-36AN")
      (description "BitFury 2016 16 nm")
      (libsource (lib "BitCoin") (part "IC_BITFURY16"))
    )
    (comp (ref "U27")
      (value "IC_BITFURY16")
      (footprint "SMD_QFN50P600X600X175-36AN")
      (description "BitFury 2016 16 nm")
      (libsource (lib "BitCoin") (part "IC_BITFURY16"))
    )
    (comp (ref "U28")
      (value "IC_BITFURY16")
      (footprint "SMD_QFN50P600X600X175-36AN")
      (description "BitFury 2016 16 nm")
      (libsource (lib "BitCoin") (part "IC_BITFURY16"))
    )
    (comp (ref "U29")
      (value "IC_BITFURY16")
      (footprint "SMD_QFN50P600X600X175-36AN")
      (description "BitFury 2016 16 nm")
      (libsource (lib "BitCoin") (part "IC_BITFURY16"))
    )
    (comp (ref "U33")
      (value "IC_BTC250")
      (footprint "SMD_QFN40P500X500X80-41N")
      (libsource (lib "BitCoin") (part "IC_BTC250"))
    )
  )
  (nets
    (net (code "1") (name "/BF_CLK5") (class "Default")
      (node (ref "U25") (pin "22") (pinfunction "SCK_22") (pintype "passive"))
      (node (ref "U33") (pin "10") (pinfunction "C_0_10") (pintype "passive"))
    )
    (net (code "2") (name "/BF_CLK6") (class "Default")
      (node (ref "U26") (pin "22") (pinfunction "SCK_22") (pintype "passive"))
      (node (ref "U33") (pin "7") (pinfunction "C_1_7") (pintype "passive"))
    )
    (net (code "3") (name "/BF_CLK7") (class "Default")
      (node (ref "U27") (pin "22") (pinfunction "SCK_22") (pintype "passive"))
      (node (ref "U33") (pin "4") (pinfunction "C_2_4") (pintype "passive"))
    )
    (net (code "4") (name "/BF_CLK8") (class "Default")
      (node (ref "U28") (pin "22") (pinfunction "SCK_22") (pintype "passive"))
      (node (ref "U33") (pin "1") (pinfunction "C_3_1") (pintype "passive"))
    )
    (net (code "5") (name "/BF_CLK9") (class "Default")
      (node (ref "U18") (pin "22") (pinfunction "SCK_22") (pintype "passive"))
      (node (ref "U33") (pin "38") (pinfunction "C_4_38") (pintype "passive"))
    )
    (net (code "6") (name "/BF_CLK10") (class "Default")
      (node (ref "U19") (pin "22") (pinfunction "SCK_22") (pintype "passive"))
      (node (ref "U33") (pin "35") (pinfunction "C_5_35") (pintype "passive"))
    )
    (net (code "7") (name "/BF_CLK11") (class "Default")
      (node (ref "U20") (pin "22") (pinfunction "SCK_22") (pintype "passive"))
      (node (ref "U33") (pin "32") (pinfunction "C_6_32") (pintype "passive"))
    )
    (net (code "8") (name "/BF_CLK12") (class "Default")
      (node (ref "U22") (pin "22") (pinfunction "SCK_22") (pintype "passive"))
      (node (ref "U33") (pin "29") (pinfunction "C_7_29") (pintype "passive"))
    )
    (net (code "9") (name "/BF_CLK13") (class "Default")
      (node (ref "U23") (pin "22") (pinfunction "SCK_22") (pintype "passive"))
      (node (ref "U33") (pin "26") (pinfunction "C_8_26") (pintype "passive"))
    )
    (net (code "10") (name "/BF_CLK14") (class "Default")
      (node (ref "U24") (pin "22") (pinfunction "SCK_22") (pintype "passive"))
      (node (ref "U33") (pin "23") (pinfunction "C_9_23") (pintype "passive"))
    )
    (net (code "11") (name "/BF_CLK15") (class "Default")
      (node (ref "U29") (pin "22") (pinfunction "SCK_22") (pintype "passive"))
      (node (ref "U33") (pin "20") (pinfunction "C_10_20") (pintype "passive"))
    )
    (net (code "12") (name "/BF_DAT5") (class "Default")
      (node (ref "U25") (pin "23") (pinfunction "SDATA_23") (pintype "passive"))
      (node (ref "U33") (pin "9") (pinfunction "D_0_9") (pintype "passive"))
    )
    (net (code "13") (name "/BF_DAT6") (class "Default")
      (node (ref "U26") (pin "23") (pinfunction "SDATA_23") (pintype "passive"))
      (node (ref "U33") (pin "6") (pinfunction "D_1_6") (pintype "passive"))
    )
    (net (code "14") (name "/BF_DAT7") (class "Default")
      (node (ref "U27") (pin "23") (pinfunction "SDATA_23") (pintype "passive"))
      (node (ref "U33") (pin "3") (pinfunction "D_2_3") (pintype "passive"))
    )
    (net (code "15") (name "/BF_DAT8") (class "Default")
      (node (ref "U28") (pin "23") (pinfunction "SDATA_23") (pintype "passive"))
      (node (ref "U33") (pin "40") (pinfunction "D_3_40") (pintype "passive"))
    )
    (net (code "16") (name "/BF_DAT9") (class "Default")
      (node (ref "U18") (pin "23") (pinfunction "SDATA_23") (pintype "passive"))
      (node (ref "U33") (pin "37") (pinfunction "D_4_37") (pintype "passive"))
    )
    (net (code "17") (name "/BF_DAT10") (class "Default")
      (node (ref "U19") (pin "23") (pinfunction "SDATA_23") (pintype "passive"))
      (node (ref "U33") (pin "34") (pinfunction "D_5_34") (pintype "passive"))
    )
    (net (code "18") (name "/BF_DAT11") (class "Default")
      (node (ref "U20") (pin "23") (pinfunction "SDATA_23") (pintype "passive"))
      (node (ref "U33") (pin "31") (pinfunction "D_6_31") (pintype "passive"))
    )
    (net (code "19") (name "/BF_DAT12") (class "Default")
      (node (ref "U22") (pin "23") (pinfunction "SDATA_23") (pintype "passive"))
      (node (ref "U33") (pin "28") (pinfunction "D_7_28") (pintype "passive"))
    )
    (net (code "20") (name "/BF_DAT13") (class "Default")
      (node (ref "U23") (pin "23") (pinfunction "SDATA_23") (pintype "passive"))
      (node (ref "U33") (pin "25") (pinfunction "D_8_25") (pintype "passive"))
    )
    (net (code "21") (name "/BF_DAT14") (class "Default")
      (node (ref "U24") (pin "23") (pinfunction "SDATA_23") (pintype "passive"))
      (node (ref "U33") (pin "22") (pinfunction "D_9_22") (pintype "passive"))
    )
    (net (code "22") (name "/BF_DAT15") (class "Default")
      (node (ref "U29") (pin "23") (pinfunction "SDATA_23") (pintype "passive"))
      (node (ref "U33") (pin "19") (pinfunction "D_10_19") (pintype "passive"))
    )
    (net (code "23") (name "/PAR_2") (class "Default")
      (node (ref "U33") (pin "18") (pinfunction "PARITY_18") (pintype "passive"))
    )
    (net (code "24") (name "/PWR5") (class "Default")
      (node (ref "C139") (pin "2") (pinfunction "2_2") (pintype "passive"))
      (node (ref "C140") (pin "2") (pinfunction "2_2") (pintype "passive"))
      (node (ref "C141") (pin "2") (pinfunction "2_2") (pintype "passive"))
      (node (ref "C151") (pin "2") (pinfunction "2_2") (pintype "passive"))
      (node (ref "C152") (pin "2") (pinfunction "2_2") (pintype "passive"))
      (node (ref "C153") (pin "2") (pinfunction "2_2") (pintype "passive"))
      (node (ref "C187") (pin "2") (pinfunction "2_2") (pintype "passive"))
      (node (ref "U25") (pin "36") (pinfunction "EP_36") (pintype "passive"))
      (node (ref "U33") (pin "41") (pinfunction "VSS_41") (pintype "passive"))
    )
    (net (code "25") (name "/PWR6") (class "Default")
      (node (ref "C139") (pin "1") (pinfunction "1_1") (pintype "passive"))
      (node (ref "C140") (pin "1") (pinfunction "1_1") (pintype "passive"))
      (node (ref "C141") (pin "1") (pinfunction "1_1") (pintype "passive"))
      (node (ref "C142") (pin "2") (pinfunction "2_2") (pintype "passive"))
      (node (ref "C143") (pin "2") (pinfunction "2_2") (pintype "passive"))
      (node (ref "C144") (pin "2") (pinfunction "2_2") (pintype "passive"))
      (node (ref "C151") (pin "1") (pinfunction "1_1") (pintype "passive"))
      (node (ref "C152") (pin "1") (pinfunction "1_1") (pintype "passive"))
      (node (ref "C153") (pin "1") (pinfunction "1_1") (pintype "passive"))
      (node (ref "C154") (pin "2") (pinfunction "2_2") (pintype "passive"))
      (node (ref "C155") (pin "2") (pinfunction "2_2") (pintype "passive"))
      (node (ref "C156") (pin "2") (pinfunction "2_2") (pintype "passive"))
      (node (ref "U25") (pin "1") (pinfunction "VDD_1") (pintype "passive"))
      (node (ref "U25") (pin "10") (pinfunction "VDD_10") (pintype "passive"))
      (node (ref "U25") (pin "11") (pinfunction "VDD_11") (pintype "passive"))
      (node (ref "U25") (pin "12") (pinfunction "VDD_12") (pintype "passive"))
      (node (ref "U25") (pin "13") (pinfunction "VDD_13") (pintype "passive"))
      (node (ref "U25") (pin "14") (pinfunction "VDD_14") (pintype "passive"))
      (node (ref "U25") (pin "15") (pinfunction "VDD_15") (pintype "passive"))
      (node (ref "U25") (pin "16") (pinfunction "VDD_16") (pintype "passive"))
      (node (ref "U25") (pin "17") (pinfunction "VDD_17") (pintype "passive"))
      (node (ref "U25") (pin "18") (pinfunction "VDD_18") (pintype "passive"))
      (node (ref "U25") (pin "19") (pinfunction "VDD_19") (pintype "passive"))
      (node (ref "U25") (pin "2") (pinfunction "VDD_2") (pintype "passive"))
      (node (ref "U25") (pin "20") (pinfunction "VDD_20") (pintype "passive"))
      (node (ref "U25") (pin "21") (pinfunction "VDD_21") (pintype "passive"))
      (node (ref "U25") (pin "24") (pinfunction "VDD_24") (pintype "passive"))
      (node (ref "U25") (pin "25") (pinfunction "VDD_25") (pintype "passive"))
      (node (ref "U25") (pin "26") (pinfunction "VDD_26") (pintype "passive"))
      (node (ref "U25") (pin "27") (pinfunction "VDD_27") (pintype "passive"))
      (node (ref "U25") (pin "28") (pinfunction "VDD_28") (pintype "passive"))
      (node (ref "U25") (pin "29") (pinfunction "VDD_29") (pintype "passive"))
      (node (ref "U25") (pin "3") (pinfunction "VDD_3") (pintype "passive"))
      (node (ref "U25") (pin "30") (pinfunction "VDD_30") (pintype "passive"))
      (node (ref "U25") (pin "31") (pinfunction "VDD_31") (pintype "passive"))
      (node (ref "U25") (pin "32") (pinfunction "VDD_32") (pintype "passive"))
      (node (ref "U25") (pin "33") (pinfunction "VDD_33") (pintype "passive"))
      (node (ref "U25") (pin "34") (pinfunction "VDD_34") (pintype "passive"))
      (node (ref "U25") (pin "35") (pinfunction "VDD_35") (pintype "passive"))
      (node (ref "U25") (pin "4") (pinfunction "VDD_4") (pintype "passive"))
      (node (ref "U25") (pin "5") (pinfunction "VDD_5") (pintype "passive"))
      (node (ref "U25") (pin "6") (pinfunction "VDD_6") (pintype "passive"))
      (node (ref "U25") (pin "7") (pinfunction "VDD_7") (pintype "passive"))
      (node (ref "U25") (pin "8") (pinfunction "VDD_8") (pintype "passive"))
      (node (ref "U25") (pin "9") (pinfunction "VDD_9") (pintype "passive"))
      (node (ref "U26") (pin "36") (pinfunction "EP_36") (pintype "passive"))
      (node (ref "U33") (pin "8") (pinfunction "V_0_8") (pintype "passive"))
    )
    (net (code "26") (name "/PWR7") (class "Default")
      (node (ref "C142") (pin "1") (pinfunction "1_1") (pintype "passive"))
      (node (ref "C143") (pin "1") (pinfunction "1_1") (pintype "passive"))
      (node (ref "C144") (pin "1") (pinfunction "1_1") (pintype "passive"))
      (node (ref "C145") (pin "2") (pinfunction "2_2") (pintype "passive"))
      (node (ref "C146") (pin "2") (pinfunction "2_2") (pintype "passive"))
      (node (ref "C147") (pin "2") (pinfunction "2_2") (pintype "passive"))
      (node (ref "C154") (pin "1") (pinfunction "1_1") (pintype "passive"))
      (node (ref "C155") (pin "1") (pinfunction "1_1") (pintype "passive"))
      (node (ref "C156") (pin "1") (pinfunction "1_1") (pintype "passive"))
      (node (ref "C157") (pin "2") (pinfunction "2_2") (pintype "passive"))
      (node (ref "C158") (pin "2") (pinfunction "2_2") (pintype "passive"))
      (node (ref "C159") (pin "2") (pinfunction "2_2") (pintype "passive"))
      (node (ref "U26") (pin "1") (pinfunction "VDD_1") (pintype "passive"))
      (node (ref "U26") (pin "10") (pinfunction "VDD_10") (pintype "passive"))
      (node (ref "U26") (pin "11") (pinfunction "VDD_11") (pintype "passive"))
      (node (ref "U26") (pin "12") (pinfunction "VDD_12") (pintype "passive"))
      (node (ref "U26") (pin "13") (pinfunction "VDD_13") (pintype "passive"))
      (node (ref "U26") (pin "14") (pinfunction "VDD_14") (pintype "passive"))
      (node (ref "U26") (pin "15") (pinfunction "VDD_15") (pintype "passive"))
      (node (ref "U26") (pin "16") (pinfunction "VDD_16") (pintype "passive"))
      (node (ref "U26") (pin "17") (pinfunction "VDD_17") (pintype "passive"))
      (node (ref "U26") (pin "18") (pinfunction "VDD_18") (pintype "passive"))
      (node (ref "U26") (pin "19") (pinfunction "VDD_19") (pintype "passive"))
      (node (ref "U26") (pin "2") (pinfunction "VDD_2") (pintype "passive"))
      (node (ref "U26") (pin "20") (pinfunction "VDD_20") (pintype "passive"))
      (node (ref "U26") (pin "21") (pinfunction "VDD_21") (pintype "passive"))
      (node (ref "U26") (pin "24") (pinfunction "VDD_24") (pintype "passive"))
      (node (ref "U26") (pin "25") (pinfunction "VDD_25") (pintype "passive"))
      (node (ref "U26") (pin "26") (pinfunction "VDD_26") (pintype "passive"))
      (node (ref "U26") (pin "27") (pinfunction "VDD_27") (pintype "passive"))
      (node (ref "U26") (pin "28") (pinfunction "VDD_28") (pintype "passive"))
      (node (ref "U26") (pin "29") (pinfunction "VDD_29") (pintype "passive"))
      (node (ref "U26") (pin "3") (pinfunction "VDD_3") (pintype "passive"))
      (node (ref "U26") (pin "30") (pinfunction "VDD_30") (pintype "passive"))
      (node (ref "U26") (pin "31") (pinfunction "VDD_31") (pintype "passive"))
      (node (ref "U26") (pin "32") (pinfunction "VDD_32") (pintype "passive"))
      (node (ref "U26") (pin "33") (pinfunction "VDD_33") (pintype "passive"))
      (node (ref "U26") (pin "34") (pinfunction "VDD_34") (pintype "passive"))
      (node (ref "U26") (pin "35") (pinfunction "VDD_35") (pintype "passive"))
      (node (ref "U26") (pin "4") (pinfunction "VDD_4") (pintype "passive"))
      (node (ref "U26") (pin "5") (pinfunction "VDD_5") (pintype "passive"))
      (node (ref "U26") (pin "6") (pinfunction "VDD_6") (pintype "passive"))
      (node (ref "U26") (pin "7") (pinfunction "VDD_7") (pintype "passive"))
      (node (ref "U26") (pin "8") (pinfunction "VDD_8") (pintype "passive"))
      (node (ref "U26") (pin "9") (pinfunction "VDD_9") (pintype "passive"))
      (node (ref "U27") (pin "36") (pinfunction "EP_36") (pintype "passive"))
      (node (ref "U33") (pin "5") (pinfunction "V_1_5") (pintype "passive"))
    )
    (net (code "27") (name "/PWR8") (class "Default")
      (node (ref "C145") (pin "1") (pinfunction "1_1") (pintype "passive"))
      (node (ref "C146") (pin "1") (pinfunction "1_1") (pintype "passive"))
      (node (ref "C147") (pin "1") (pinfunction "1_1") (pintype "passive"))
      (node (ref "C148") (pin "2") (pinfunction "2_2") (pintype "passive"))
      (node (ref "C149") (pin "2") (pinfunction "2_2") (pintype "passive"))
      (node (ref "C150") (pin "2") (pinfunction "2_2") (pintype "passive"))
      (node (ref "C157") (pin "1") (pinfunction "1_1") (pintype "passive"))
      (node (ref "C158") (pin "1") (pinfunction "1_1") (pintype "passive"))
      (node (ref "C159") (pin "1") (pinfunction "1_1") (pintype "passive"))
      (node (ref "C160") (pin "2") (pinfunction "2_2") (pintype "passive"))
      (node (ref "C161") (pin "2") (pinfunction "2_2") (pintype "passive"))
      (node (ref "C162") (pin "2") (pinfunction "2_2") (pintype "passive"))
      (node (ref "U27") (pin "1") (pinfunction "VDD_1") (pintype "passive"))
      (node (ref "U27") (pin "10") (pinfunction "VDD_10") (pintype "passive"))
      (node (ref "U27") (pin "11") (pinfunction "VDD_11") (pintype "passive"))
      (node (ref "U27") (pin "12") (pinfunction "VDD_12") (pintype "passive"))
      (node (ref "U27") (pin "13") (pinfunction "VDD_13") (pintype "passive"))
      (node (ref "U27") (pin "14") (pinfunction "VDD_14") (pintype "passive"))
      (node (ref "U27") (pin "15") (pinfunction "VDD_15") (pintype "passive"))
      (node (ref "U27") (pin "16") (pinfunction "VDD_16") (pintype "passive"))
      (node (ref "U27") (pin "17") (pinfunction "VDD_17") (pintype "passive"))
      (node (ref "U27") (pin "18") (pinfunction "VDD_18") (pintype "passive"))
      (node (ref "U27") (pin "19") (pinfunction "VDD_19") (pintype "passive"))
      (node (ref "U27") (pin "2") (pinfunction "VDD_2") (pintype "passive"))
      (node (ref "U27") (pin "20") (pinfunction "VDD_20") (pintype "passive"))
      (node (ref "U27") (pin "21") (pinfunction "VDD_21") (pintype "passive"))
      (node (ref "U27") (pin "24") (pinfunction "VDD_24") (pintype "passive"))
      (node (ref "U27") (pin "25") (pinfunction "VDD_25") (pintype "passive"))
      (node (ref "U27") (pin "26") (pinfunction "VDD_26") (pintype "passive"))
      (node (ref "U27") (pin "27") (pinfunction "VDD_27") (pintype "passive"))
      (node (ref "U27") (pin "28") (pinfunction "VDD_28") (pintype "passive"))
      (node (ref "U27") (pin "29") (pinfunction "VDD_29") (pintype "passive"))
      (node (ref "U27") (pin "3") (pinfunction "VDD_3") (pintype "passive"))
      (node (ref "U27") (pin "30") (pinfunction "VDD_30") (pintype "passive"))
      (node (ref "U27") (pin "31") (pinfunction "VDD_31") (pintype "passive"))
      (node (ref "U27") (pin "32") (pinfunction "VDD_32") (pintype "passive"))
      (node (ref "U27") (pin "33") (pinfunction "VDD_33") (pintype "passive"))
      (node (ref "U27") (pin "34") (pinfunction "VDD_34") (pintype "passive"))
      (node (ref "U27") (pin "35") (pinfunction "VDD_35") (pintype "passive"))
      (node (ref "U27") (pin "4") (pinfunction "VDD_4") (pintype "passive"))
      (node (ref "U27") (pin "5") (pinfunction "VDD_5") (pintype "passive"))
      (node (ref "U27") (pin "6") (pinfunction "VDD_6") (pintype "passive"))
      (node (ref "U27") (pin "7") (pinfunction "VDD_7") (pintype "passive"))
      (node (ref "U27") (pin "8") (pinfunction "VDD_8") (pintype "passive"))
      (node (ref "U27") (pin "9") (pinfunction "VDD_9") (pintype "passive"))
      (node (ref "U28") (pin "36") (pinfunction "EP_36") (pintype "passive"))
      (node (ref "U33") (pin "2") (pinfunction "V_2_2") (pintype "passive"))
    )
    (net (code "28") (name "/PWR9") (class "Default")
      (node (ref "C100") (pin "2") (pinfunction "2_2") (pintype "passive"))
      (node (ref "C101") (pin "2") (pinfunction "2_2") (pintype "passive"))
      (node (ref "C114") (pin "2") (pinfunction "2_2") (pintype "passive"))
      (node (ref "C115") (pin "2") (pinfunction "2_2") (pintype "passive"))
      (node (ref "C116") (pin "2") (pinfunction "2_2") (pintype "passive"))
      (node (ref "C148") (pin "1") (pinfunction "1_1") (pintype "passive"))
      (node (ref "C149") (pin "1") (pinfunction "1_1") (pintype "passive"))
      (node (ref "C150") (pin "1") (pinfunction "1_1") (pintype "passive"))
      (node (ref "C160") (pin "1") (pinfunction "1_1") (pintype "passive"))
      (node (ref "C161") (pin "1") (pinfunction "1_1") (pintype "passive"))
      (node (ref "C162") (pin "1") (pinfunction "1_1") (pintype "passive"))
      (node (ref "C99") (pin "2") (pinfunction "2_2") (pintype "passive"))
      (node (ref "U18") (pin "36") (pinfunction "EP_36") (pintype "passive"))
      (node (ref "U28") (pin "1") (pinfunction "VDD_1") (pintype "passive"))
      (node (ref "U28") (pin "10") (pinfunction "VDD_10") (pintype "passive"))
      (node (ref "U28") (pin "11") (pinfunction "VDD_11") (pintype "passive"))
      (node (ref "U28") (pin "12") (pinfunction "VDD_12") (pintype "passive"))
      (node (ref "U28") (pin "13") (pinfunction "VDD_13") (pintype "passive"))
      (node (ref "U28") (pin "14") (pinfunction "VDD_14") (pintype "passive"))
      (node (ref "U28") (pin "15") (pinfunction "VDD_15") (pintype "passive"))
      (node (ref "U28") (pin "16") (pinfunction "VDD_16") (pintype "passive"))
      (node (ref "U28") (pin "17") (pinfunction "VDD_17") (pintype "passive"))
      (node (ref "U28") (pin "18") (pinfunction "VDD_18") (pintype "passive"))
      (node (ref "U28") (pin "19") (pinfunction "VDD_19") (pintype "passive"))
      (node (ref "U28") (pin "2") (pinfunction "VDD_2") (pintype "passive"))
      (node (ref "U28") (pin "20") (pinfunction "VDD_20") (pintype "passive"))
      (node (ref "U28") (pin "21") (pinfunction "VDD_21") (pintype "passive"))
      (node (ref "U28") (pin "24") (pinfunction "VDD_24") (pintype "passive"))
      (node (ref "U28") (pin "25") (pinfunction "VDD_25") (pintype "passive"))
      (node (ref "U28") (pin "26") (pinfunction "VDD_26") (pintype "passive"))
      (node (ref "U28") (pin "27") (pinfunction "VDD_27") (pintype "passive"))
      (node (ref "U28") (pin "28") (pinfunction "VDD_28") (pintype "passive"))
      (node (ref "U28") (pin "29") (pinfunction "VDD_29") (pintype "passive"))
      (node (ref "U28") (pin "3") (pinfunction "VDD_3") (pintype "passive"))
      (node (ref "U28") (pin "30") (pinfunction "VDD_30") (pintype "passive"))
      (node (ref "U28") (pin "31") (pinfunction "VDD_31") (pintype "passive"))
      (node (ref "U28") (pin "32") (pinfunction "VDD_32") (pintype "passive"))
      (node (ref "U28") (pin "33") (pinfunction "VDD_33") (pintype "passive"))
      (node (ref "U28") (pin "34") (pinfunction "VDD_34") (pintype "passive"))
      (node (ref "U28") (pin "35") (pinfunction "VDD_35") (pintype "passive"))
      (node (ref "U28") (pin "4") (pinfunction "VDD_4") (pintype "passive"))
      (node (ref "U28") (pin "5") (pinfunction "VDD_5") (pintype "passive"))
      (node (ref "U28") (pin "6") (pinfunction "VDD_6") (pintype "passive"))
      (node (ref "U28") (pin "7") (pinfunction "VDD_7") (pintype "passive"))
      (node (ref "U28") (pin "8") (pinfunction "VDD_8") (pintype "passive"))
      (node (ref "U28") (pin "9") (pinfunction "VDD_9") (pintype "passive"))
      (node (ref "U33") (pin "39") (pinfunction "V_3_39") (pintype "passive"))
    )
    (net (code "29") (name "/PWR10") (class "Default")
      (node (ref "C100") (pin "1") (pinfunction "1_1") (pintype "passive"))
      (node (ref "C101") (pin "1") (pinfunction "1_1") (pintype "passive"))
      (node (ref "C102") (pin "2") (pinfunction "2_2") (pintype "passive"))
      (node (ref "C103") (pin "2") (pinfunction "2_2") (pintype "passive"))
      (node (ref "C104") (pin "2") (pinfunction "2_2") (pintype "passive"))
      (node (ref "C114") (pin "1") (pinfunction "1_1") (pintype "passive"))
      (node (ref "C115") (pin "1") (pinfunction "1_1") (pintype "passive"))
      (node (ref "C116") (pin "1") (pinfunction "1_1") (pintype "passive"))
      (node (ref "C117") (pin "2") (pinfunction "2_2") (pintype "passive"))
      (node (ref "C118") (pin "2") (pinfunction "2_2") (pintype "passive"))
      (node (ref "C119") (pin "2") (pinfunction "2_2") (pintype "passive"))
      (node (ref "C99") (pin "1") (pinfunction "1_1") (pintype "passive"))
      (node (ref "U18") (pin "1") (pinfunction "VDD_1") (pintype "passive"))
      (node (ref "U18") (pin "10") (pinfunction "VDD_10") (pintype "passive"))
      (node (ref "U18") (pin "11") (pinfunction "VDD_11") (pintype "passive"))
      (node (ref "U18") (pin "12") (pinfunction "VDD_12") (pintype "passive"))
      (node (ref "U18") (pin "13") (pinfunction "VDD_13") (pintype "passive"))
      (node (ref "U18") (pin "14") (pinfunction "VDD_14") (pintype "passive"))
      (node (ref "U18") (pin "15") (pinfunction "VDD_15") (pintype "passive"))
      (node (ref "U18") (pin "16") (pinfunction "VDD_16") (pintype "passive"))
      (node (ref "U18") (pin "17") (pinfunction "VDD_17") (pintype "passive"))
      (node (ref "U18") (pin "18") (pinfunction "VDD_18") (pintype "passive"))
      (node (ref "U18") (pin "19") (pinfunction "VDD_19") (pintype "passive"))
      (node (ref "U18") (pin "2") (pinfunction "VDD_2") (pintype "passive"))
      (node (ref "U18") (pin "20") (pinfunction "VDD_20") (pintype "passive"))
      (node (ref "U18") (pin "21") (pinfunction "VDD_21") (pintype "passive"))
      (node (ref "U18") (pin "24") (pinfunction "VDD_24") (pintype "passive"))
      (node (ref "U18") (pin "25") (pinfunction "VDD_25") (pintype "passive"))
      (node (ref "U18") (pin "26") (pinfunction "VDD_26") (pintype "passive"))
      (node (ref "U18") (pin "27") (pinfunction "VDD_27") (pintype "passive"))
      (node (ref "U18") (pin "28") (pinfunction "VDD_28") (pintype "passive"))
      (node (ref "U18") (pin "29") (pinfunction "VDD_29") (pintype "passive"))
      (node (ref "U18") (pin "3") (pinfunction "VDD_3") (pintype "passive"))
      (node (ref "U18") (pin "30") (pinfunction "VDD_30") (pintype "passive"))
      (node (ref "U18") (pin "31") (pinfunction "VDD_31") (pintype "passive"))
      (node (ref "U18") (pin "32") (pinfunction "VDD_32") (pintype "passive"))
      (node (ref "U18") (pin "33") (pinfunction "VDD_33") (pintype "passive"))
      (node (ref "U18") (pin "34") (pinfunction "VDD_34") (pintype "passive"))
      (node (ref "U18") (pin "35") (pinfunction "VDD_35") (pintype "passive"))
      (node (ref "U18") (pin "4") (pinfunction "VDD_4") (pintype "passive"))
      (node (ref "U18") (pin "5") (pinfunction "VDD_5") (pintype "passive"))
      (node (ref "U18") (pin "6") (pinfunction "VDD_6") (pintype "passive"))
      (node (ref "U18") (pin "7") (pinfunction "VDD_7") (pintype "passive"))
      (node (ref "U18") (pin "8") (pinfunction "VDD_8") (pintype "passive"))
      (node (ref "U18") (pin "9") (pinfunction "VDD_9") (pintype "passive"))
      (node (ref "U19") (pin "36") (pinfunction "EP_36") (pintype "passive"))
      (node (ref "U33") (pin "36") (pinfunction "V_4_36") (pintype "passive"))
    )
    (net (code "30") (name "/PWR11") (class "Default")
      (node (ref "C102") (pin "1") (pinfunction "1_1") (pintype "passive"))
      (node (ref "C103") (pin "1") (pinfunction "1_1") (pintype "passive"))
      (node (ref "C104") (pin "1") (pinfunction "1_1") (pintype "passive"))
      (node (ref "C105") (pin "2") (pinfunction "2_2") (pintype "passive"))
      (node (ref "C106") (pin "2") (pinfunction "2_2") (pintype "passive"))
      (node (ref "C107") (pin "2") (pinfunction "2_2") (pintype "passive"))
      (node (ref "C117") (pin "1") (pinfunction "1_1") (pintype "passive"))
      (node (ref "C118") (pin "1") (pinfunction "1_1") (pintype "passive"))
      (node (ref "C119") (pin "1") (pinfunction "1_1") (pintype "passive"))
      (node (ref "C121") (pin "2") (pinfunction "2_2") (pintype "passive"))
      (node (ref "C122") (pin "2") (pinfunction "2_2") (pintype "passive"))
      (node (ref "C123") (pin "2") (pinfunction "2_2") (pintype "passive"))
      (node (ref "U19") (pin "1") (pinfunction "VDD_1") (pintype "passive"))
      (node (ref "U19") (pin "10") (pinfunction "VDD_10") (pintype "passive"))
      (node (ref "U19") (pin "11") (pinfunction "VDD_11") (pintype "passive"))
      (node (ref "U19") (pin "12") (pinfunction "VDD_12") (pintype "passive"))
      (node (ref "U19") (pin "13") (pinfunction "VDD_13") (pintype "passive"))
      (node (ref "U19") (pin "14") (pinfunction "VDD_14") (pintype "passive"))
      (node (ref "U19") (pin "15") (pinfunction "VDD_15") (pintype "passive"))
      (node (ref "U19") (pin "16") (pinfunction "VDD_16") (pintype "passive"))
      (node (ref "U19") (pin "17") (pinfunction "VDD_17") (pintype "passive"))
      (node (ref "U19") (pin "18") (pinfunction "VDD_18") (pintype "passive"))
      (node (ref "U19") (pin "19") (pinfunction "VDD_19") (pintype "passive"))
      (node (ref "U19") (pin "2") (pinfunction "VDD_2") (pintype "passive"))
      (node (ref "U19") (pin "20") (pinfunction "VDD_20") (pintype "passive"))
      (node (ref "U19") (pin "21") (pinfunction "VDD_21") (pintype "passive"))
      (node (ref "U19") (pin "24") (pinfunction "VDD_24") (pintype "passive"))
      (node (ref "U19") (pin "25") (pinfunction "VDD_25") (pintype "passive"))
      (node (ref "U19") (pin "26") (pinfunction "VDD_26") (pintype "passive"))
      (node (ref "U19") (pin "27") (pinfunction "VDD_27") (pintype "passive"))
      (node (ref "U19") (pin "28") (pinfunction "VDD_28") (pintype "passive"))
      (node (ref "U19") (pin "29") (pinfunction "VDD_29") (pintype "passive"))
      (node (ref "U19") (pin "3") (pinfunction "VDD_3") (pintype "passive"))
      (node (ref "U19") (pin "30") (pinfunction "VDD_30") (pintype "passive"))
      (node (ref "U19") (pin "31") (pinfunction "VDD_31") (pintype "passive"))
      (node (ref "U19") (pin "32") (pinfunction "VDD_32") (pintype "passive"))
      (node (ref "U19") (pin "33") (pinfunction "VDD_33") (pintype "passive"))
      (node (ref "U19") (pin "34") (pinfunction "VDD_34") (pintype "passive"))
      (node (ref "U19") (pin "35") (pinfunction "VDD_35") (pintype "passive"))
      (node (ref "U19") (pin "4") (pinfunction "VDD_4") (pintype "passive"))
      (node (ref "U19") (pin "5") (pinfunction "VDD_5") (pintype "passive"))
      (node (ref "U19") (pin "6") (pinfunction "VDD_6") (pintype "passive"))
      (node (ref "U19") (pin "7") (pinfunction "VDD_7") (pintype "passive"))
      (node (ref "U19") (pin "8") (pinfunction "VDD_8") (pintype "passive"))
      (node (ref "U19") (pin "9") (pinfunction "VDD_9") (pintype "passive"))
      (node (ref "U20") (pin "36") (pinfunction "EP_36") (pintype "passive"))
      (node (ref "U33") (pin "33") (pinfunction "V_5_33") (pintype "passive"))
    )
    (net (code "31") (name "/PWR12") (class "Default")
      (node (ref "C105") (pin "1") (pinfunction "1_1") (pintype "passive"))
      (node (ref "C106") (pin "1") (pinfunction "1_1") (pintype "passive"))
      (node (ref "C107") (pin "1") (pinfunction "1_1") (pintype "passive"))
      (node (ref "C111") (pin "2") (pinfunction "2_2") (pintype "passive"))
      (node (ref "C112") (pin "2") (pinfunction "2_2") (pintype "passive"))
      (node (ref "C113") (pin "2") (pinfunction "2_2") (pintype "passive"))
      (node (ref "C121") (pin "1") (pinfunction "1_1") (pintype "passive"))
      (node (ref "C122") (pin "1") (pinfunction "1_1") (pintype "passive"))
      (node (ref "C123") (pin "1") (pinfunction "1_1") (pintype "passive"))
      (node (ref "C124") (pin "2") (pinfunction "2_2") (pintype "passive"))
      (node (ref "C125") (pin "2") (pinfunction "2_2") (pintype "passive"))
      (node (ref "C126") (pin "2") (pinfunction "2_2") (pintype "passive"))
      (node (ref "U20") (pin "1") (pinfunction "VDD_1") (pintype "passive"))
      (node (ref "U20") (pin "10") (pinfunction "VDD_10") (pintype "passive"))
      (node (ref "U20") (pin "11") (pinfunction "VDD_11") (pintype "passive"))
      (node (ref "U20") (pin "12") (pinfunction "VDD_12") (pintype "passive"))
      (node (ref "U20") (pin "13") (pinfunction "VDD_13") (pintype "passive"))
      (node (ref "U20") (pin "14") (pinfunction "VDD_14") (pintype "passive"))
      (node (ref "U20") (pin "15") (pinfunction "VDD_15") (pintype "passive"))
      (node (ref "U20") (pin "16") (pinfunction "VDD_16") (pintype "passive"))
      (node (ref "U20") (pin "17") (pinfunction "VDD_17") (pintype "passive"))
      (node (ref "U20") (pin "18") (pinfunction "VDD_18") (pintype "passive"))
      (node (ref "U20") (pin "19") (pinfunction "VDD_19") (pintype "passive"))
      (node (ref "U20") (pin "2") (pinfunction "VDD_2") (pintype "passive"))
      (node (ref "U20") (pin "20") (pinfunction "VDD_20") (pintype "passive"))
      (node (ref "U20") (pin "21") (pinfunction "VDD_21") (pintype "passive"))
      (node (ref "U20") (pin "24") (pinfunction "VDD_24") (pintype "passive"))
      (node (ref "U20") (pin "25") (pinfunction "VDD_25") (pintype "passive"))
      (node (ref "U20") (pin "26") (pinfunction "VDD_26") (pintype "passive"))
      (node (ref "U20") (pin "27") (pinfunction "VDD_27") (pintype "passive"))
      (node (ref "U20") (pin "28") (pinfunction "VDD_28") (pintype "passive"))
      (node (ref "U20") (pin "29") (pinfunction "VDD_29") (pintype "passive"))
      (node (ref "U20") (pin "3") (pinfunction "VDD_3") (pintype "passive"))
      (node (ref "U20") (pin "30") (pinfunction "VDD_30") (pintype "passive"))
      (node (ref "U20") (pin "31") (pinfunction "VDD_31") (pintype "passive"))
      (node (ref "U20") (pin "32") (pinfunction "VDD_32") (pintype "passive"))
      (node (ref "U20") (pin "33") (pinfunction "VDD_33") (pintype "passive"))
      (node (ref "U20") (pin "34") (pinfunction "VDD_34") (pintype "passive"))
      (node (ref "U20") (pin "35") (pinfunction "VDD_35") (pintype "passive"))
      (node (ref "U20") (pin "4") (pinfunction "VDD_4") (pintype "passive"))
      (node (ref "U20") (pin "5") (pinfunction "VDD_5") (pintype "passive"))
      (node (ref "U20") (pin "6") (pinfunction "VDD_6") (pintype "passive"))
      (node (ref "U20") (pin "7") (pinfunction "VDD_7") (pintype "passive"))
      (node (ref "U20") (pin "8") (pinfunction "VDD_8") (pintype "passive"))
      (node (ref "U20") (pin "9") (pinfunction "VDD_9") (pintype "passive"))
      (node (ref "U22") (pin "36") (pinfunction "EP_36") (pintype "passive"))
      (node (ref "U33") (pin "30") (pinfunction "V_6_30") (pintype "passive"))
    )
    (net (code "32") (name "/PWR13") (class "Default")
      (node (ref "C111") (pin "1") (pinfunction "1_1") (pintype "passive"))
      (node (ref "C112") (pin "1") (pinfunction "1_1") (pintype "passive"))
      (node (ref "C113") (pin "1") (pinfunction "1_1") (pintype "passive"))
      (node (ref "C124") (pin "1") (pinfunction "1_1") (pintype "passive"))
      (node (ref "C125") (pin "1") (pinfunction "1_1") (pintype "passive"))
      (node (ref "C126") (pin "1") (pinfunction "1_1") (pintype "passive"))
      (node (ref "C127") (pin "2") (pinfunction "2_2") (pintype "passive"))
      (node (ref "C128") (pin "2") (pinfunction "2_2") (pintype "passive"))
      (node (ref "C129") (pin "2") (pinfunction "2_2") (pintype "passive"))
      (node (ref "C136") (pin "2") (pinfunction "2_2") (pintype "passive"))
      (node (ref "C137") (pin "2") (pinfunction "2_2") (pintype "passive"))
      (node (ref "C138") (pin "2") (pinfunction "2_2") (pintype "passive"))
      (node (ref "U22") (pin "1") (pinfunction "VDD_1") (pintype "passive"))
      (node (ref "U22") (pin "10") (pinfunction "VDD_10") (pintype "passive"))
      (node (ref "U22") (pin "11") (pinfunction "VDD_11") (pintype "passive"))
      (node (ref "U22") (pin "12") (pinfunction "VDD_12") (pintype "passive"))
      (node (ref "U22") (pin "13") (pinfunction "VDD_13") (pintype "passive"))
      (node (ref "U22") (pin "14") (pinfunction "VDD_14") (pintype "passive"))
      (node (ref "U22") (pin "15") (pinfunction "VDD_15") (pintype "passive"))
      (node (ref "U22") (pin "16") (pinfunction "VDD_16") (pintype "passive"))
      (node (ref "U22") (pin "17") (pinfunction "VDD_17") (pintype "passive"))
      (node (ref "U22") (pin "18") (pinfunction "VDD_18") (pintype "passive"))
      (node (ref "U22") (pin "19") (pinfunction "VDD_19") (pintype "passive"))
      (node (ref "U22") (pin "2") (pinfunction "VDD_2") (pintype "passive"))
      (node (ref "U22") (pin "20") (pinfunction "VDD_20") (pintype "passive"))
      (node (ref "U22") (pin "21") (pinfunction "VDD_21") (pintype "passive"))
      (node (ref "U22") (pin "24") (pinfunction "VDD_24") (pintype "passive"))
      (node (ref "U22") (pin "25") (pinfunction "VDD_25") (pintype "passive"))
      (node (ref "U22") (pin "26") (pinfunction "VDD_26") (pintype "passive"))
      (node (ref "U22") (pin "27") (pinfunction "VDD_27") (pintype "passive"))
      (node (ref "U22") (pin "28") (pinfunction "VDD_28") (pintype "passive"))
      (node (ref "U22") (pin "29") (pinfunction "VDD_29") (pintype "passive"))
      (node (ref "U22") (pin "3") (pinfunction "VDD_3") (pintype "passive"))
      (node (ref "U22") (pin "30") (pinfunction "VDD_30") (pintype "passive"))
      (node (ref "U22") (pin "31") (pinfunction "VDD_31") (pintype "passive"))
      (node (ref "U22") (pin "32") (pinfunction "VDD_32") (pintype "passive"))
      (node (ref "U22") (pin "33") (pinfunction "VDD_33") (pintype "passive"))
      (node (ref "U22") (pin "34") (pinfunction "VDD_34") (pintype "passive"))
      (node (ref "U22") (pin "35") (pinfunction "VDD_35") (pintype "passive"))
      (node (ref "U22") (pin "4") (pinfunction "VDD_4") (pintype "passive"))
      (node (ref "U22") (pin "5") (pinfunction "VDD_5") (pintype "passive"))
      (node (ref "U22") (pin "6") (pinfunction "VDD_6") (pintype "passive"))
      (node (ref "U22") (pin "7") (pinfunction "VDD_7") (pintype "passive"))
      (node (ref "U22") (pin "8") (pinfunction "VDD_8") (pintype "passive"))
      (node (ref "U22") (pin "9") (pinfunction "VDD_9") (pintype "passive"))
      (node (ref "U23") (pin "36") (pinfunction "EP_36") (pintype "passive"))
      (node (ref "U33") (pin "27") (pinfunction "V_7_27") (pintype "passive"))
    )
    (net (code "33") (name "/PWR14") (class "Default")
      (node (ref "C127") (pin "1") (pinfunction "1_1") (pintype "passive"))
      (node (ref "C128") (pin "1") (pinfunction "1_1") (pintype "passive"))
      (node (ref "C129") (pin "1") (pinfunction "1_1") (pintype "passive"))
      (node (ref "C130") (pin "2") (pinfunction "2_2") (pintype "passive"))
      (node (ref "C131") (pin "2") (pinfunction "2_2") (pintype "passive"))
      (node (ref "C132") (pin "2") (pinfunction "2_2") (pintype "passive"))
      (node (ref "C136") (pin "1") (pinfunction "1_1") (pintype "passive"))
      (node (ref "C137") (pin "1") (pinfunction "1_1") (pintype "passive"))
      (node (ref "C138") (pin "1") (pinfunction "1_1") (pintype "passive"))
      (node (ref "C163") (pin "2") (pinfunction "2_2") (pintype "passive"))
      (node (ref "C164") (pin "2") (pinfunction "2_2") (pintype "passive"))
      (node (ref "C165") (pin "2") (pinfunction "2_2") (pintype "passive"))
      (node (ref "U23") (pin "1") (pinfunction "VDD_1") (pintype "passive"))
      (node (ref "U23") (pin "10") (pinfunction "VDD_10") (pintype "passive"))
      (node (ref "U23") (pin "11") (pinfunction "VDD_11") (pintype "passive"))
      (node (ref "U23") (pin "12") (pinfunction "VDD_12") (pintype "passive"))
      (node (ref "U23") (pin "13") (pinfunction "VDD_13") (pintype "passive"))
      (node (ref "U23") (pin "14") (pinfunction "VDD_14") (pintype "passive"))
      (node (ref "U23") (pin "15") (pinfunction "VDD_15") (pintype "passive"))
      (node (ref "U23") (pin "16") (pinfunction "VDD_16") (pintype "passive"))
      (node (ref "U23") (pin "17") (pinfunction "VDD_17") (pintype "passive"))
      (node (ref "U23") (pin "18") (pinfunction "VDD_18") (pintype "passive"))
      (node (ref "U23") (pin "19") (pinfunction "VDD_19") (pintype "passive"))
      (node (ref "U23") (pin "2") (pinfunction "VDD_2") (pintype "passive"))
      (node (ref "U23") (pin "20") (pinfunction "VDD_20") (pintype "passive"))
      (node (ref "U23") (pin "21") (pinfunction "VDD_21") (pintype "passive"))
      (node (ref "U23") (pin "24") (pinfunction "VDD_24") (pintype "passive"))
      (node (ref "U23") (pin "25") (pinfunction "VDD_25") (pintype "passive"))
      (node (ref "U23") (pin "26") (pinfunction "VDD_26") (pintype "passive"))
      (node (ref "U23") (pin "27") (pinfunction "VDD_27") (pintype "passive"))
      (node (ref "U23") (pin "28") (pinfunction "VDD_28") (pintype "passive"))
      (node (ref "U23") (pin "29") (pinfunction "VDD_29") (pintype "passive"))
      (node (ref "U23") (pin "3") (pinfunction "VDD_3") (pintype "passive"))
      (node (ref "U23") (pin "30") (pinfunction "VDD_30") (pintype "passive"))
      (node (ref "U23") (pin "31") (pinfunction "VDD_31") (pintype "passive"))
      (node (ref "U23") (pin "32") (pinfunction "VDD_32") (pintype "passive"))
      (node (ref "U23") (pin "33") (pinfunction "VDD_33") (pintype "passive"))
      (node (ref "U23") (pin "34") (pinfunction "VDD_34") (pintype "passive"))
      (node (ref "U23") (pin "35") (pinfunction "VDD_35") (pintype "passive"))
      (node (ref "U23") (pin "4") (pinfunction "VDD_4") (pintype "passive"))
      (node (ref "U23") (pin "5") (pinfunction "VDD_5") (pintype "passive"))
      (node (ref "U23") (pin "6") (pinfunction "VDD_6") (pintype "passive"))
      (node (ref "U23") (pin "7") (pinfunction "VDD_7") (pintype "passive"))
      (node (ref "U23") (pin "8") (pinfunction "VDD_8") (pintype "passive"))
      (node (ref "U23") (pin "9") (pinfunction "VDD_9") (pintype "passive"))
      (node (ref "U24") (pin "36") (pinfunction "EP_36") (pintype "passive"))
      (node (ref "U33") (pin "24") (pinfunction "V_8_24") (pintype "passive"))
    )
    (net (code "34") (name "/PWR15") (class "Default")
      (node (ref "C130") (pin "1") (pinfunction "1_1") (pintype "passive"))
      (node (ref "C131") (pin "1") (pinfunction "1_1") (pintype "passive"))
      (node (ref "C132") (pin "1") (pinfunction "1_1") (pintype "passive"))
      (node (ref "C133") (pin "2") (pinfunction "2_2") (pintype "passive"))
      (node (ref "C134") (pin "2") (pinfunction "2_2") (pintype "passive"))
      (node (ref "C135") (pin "2") (pinfunction "2_2") (pintype "passive"))
      (node (ref "C163") (pin "1") (pinfunction "1_1") (pintype "passive"))
      (node (ref "C164") (pin "1") (pinfunction "1_1") (pintype "passive"))
      (node (ref "C165") (pin "1") (pinfunction "1_1") (pintype "passive"))
      (node (ref "C166") (pin "2") (pinfunction "2_2") (pintype "passive"))
      (node (ref "C167") (pin "2") (pinfunction "2_2") (pintype "passive"))
      (node (ref "C168") (pin "2") (pinfunction "2_2") (pintype "passive"))
      (node (ref "U24") (pin "1") (pinfunction "VDD_1") (pintype "passive"))
      (node (ref "U24") (pin "10") (pinfunction "VDD_10") (pintype "passive"))
      (node (ref "U24") (pin "11") (pinfunction "VDD_11") (pintype "passive"))
      (node (ref "U24") (pin "12") (pinfunction "VDD_12") (pintype "passive"))
      (node (ref "U24") (pin "13") (pinfunction "VDD_13") (pintype "passive"))
      (node (ref "U24") (pin "14") (pinfunction "VDD_14") (pintype "passive"))
      (node (ref "U24") (pin "15") (pinfunction "VDD_15") (pintype "passive"))
      (node (ref "U24") (pin "16") (pinfunction "VDD_16") (pintype "passive"))
      (node (ref "U24") (pin "17") (pinfunction "VDD_17") (pintype "passive"))
      (node (ref "U24") (pin "18") (pinfunction "VDD_18") (pintype "passive"))
      (node (ref "U24") (pin "19") (pinfunction "VDD_19") (pintype "passive"))
      (node (ref "U24") (pin "2") (pinfunction "VDD_2") (pintype "passive"))
      (node (ref "U24") (pin "20") (pinfunction "VDD_20") (pintype "passive"))
      (node (ref "U24") (pin "21") (pinfunction "VDD_21") (pintype "passive"))
      (node (ref "U24") (pin "24") (pinfunction "VDD_24") (pintype "passive"))
      (node (ref "U24") (pin "25") (pinfunction "VDD_25") (pintype "passive"))
      (node (ref "U24") (pin "26") (pinfunction "VDD_26") (pintype "passive"))
      (node (ref "U24") (pin "27") (pinfunction "VDD_27") (pintype "passive"))
      (node (ref "U24") (pin "28") (pinfunction "VDD_28") (pintype "passive"))
      (node (ref "U24") (pin "29") (pinfunction "VDD_29") (pintype "passive"))
      (node (ref "U24") (pin "3") (pinfunction "VDD_3") (pintype "passive"))
      (node (ref "U24") (pin "30") (pinfunction "VDD_30") (pintype "passive"))
      (node (ref "U24") (pin "31") (pinfunction "VDD_31") (pintype "passive"))
      (node (ref "U24") (pin "32") (pinfunction "VDD_32") (pintype "passive"))
      (node (ref "U24") (pin "33") (pinfunction "VDD_33") (pintype "passive"))
      (node (ref "U24") (pin "34") (pinfunction "VDD_34") (pintype "passive"))
      (node (ref "U24") (pin "35") (pinfunction "VDD_35") (pintype "passive"))
      (node (ref "U24") (pin "4") (pinfunction "VDD_4") (pintype "passive"))
      (node (ref "U24") (pin "5") (pinfunction "VDD_5") (pintype "passive"))
      (node (ref "U24") (pin "6") (pinfunction "VDD_6") (pintype "passive"))
      (node (ref "U24") (pin "7") (pinfunction "VDD_7") (pintype "passive"))
      (node (ref "U24") (pin "8") (pinfunction "VDD_8") (pintype "passive"))
      (node (ref "U24") (pin "9") (pinfunction "VDD_9") (pintype "passive"))
      (node (ref "U29") (pin "36") (pinfunction "EP_36") (pintype "passive"))
      (node (ref "U33") (pin "21") (pinfunction "V_9_21") (pintype "passive"))
    )
    (net (code "35") (name "/PWR16") (class "Default")
      (node (ref "C133") (pin "1") (pinfunction "1_1") (pintype "passive"))
      (node (ref "C134") (pin "1") (pinfunction "1_1") (pintype "passive"))
      (node (ref "C135") (pin "1") (pinfunction "1_1") (pintype "passive"))
      (node (ref "C166") (pin "1") (pinfunction "1_1") (pintype "passive"))
      (node (ref "C167") (pin "1") (pinfunction "1_1") (pintype "passive"))
      (node (ref "C168") (pin "1") (pinfunction "1_1") (pintype "passive"))
      (node (ref "C187") (pin "1") (pinfunction "1_1") (pintype "passive"))
      (node (ref "U29") (pin "1") (pinfunction "VDD_1") (pintype "passive"))
      (node (ref "U29") (pin "10") (pinfunction "VDD_10") (pintype "passive"))
      (node (ref "U29") (pin "11") (pinfunction "VDD_11") (pintype "passive"))
      (node (ref "U29") (pin "12") (pinfunction "VDD_12") (pintype "passive"))
      (node (ref "U29") (pin "13") (pinfunction "VDD_13") (pintype "passive"))
      (node (ref "U29") (pin "14") (pinfunction "VDD_14") (pintype "passive"))
      (node (ref "U29") (pin "15") (pinfunction "VDD_15") (pintype "passive"))
      (node (ref "U29") (pin "16") (pinfunction "VDD_16") (pintype "passive"))
      (node (ref "U29") (pin "17") (pinfunction "VDD_17") (pintype "passive"))
      (node (ref "U29") (pin "18") (pinfunction "VDD_18") (pintype "passive"))
      (node (ref "U29") (pin "19") (pinfunction "VDD_19") (pintype "passive"))
      (node (ref "U29") (pin "2") (pinfunction "VDD_2") (pintype "passive"))
      (node (ref "U29") (pin "20") (pinfunction "VDD_20") (pintype "passive"))
      (node (ref "U29") (pin "21") (pinfunction "VDD_21") (pintype "passive"))
      (node (ref "U29") (pin "24") (pinfunction "VDD_24") (pintype "passive"))
      (node (ref "U29") (pin "25") (pinfunction "VDD_25") (pintype "passive"))
      (node (ref "U29") (pin "26") (pinfunction "VDD_26") (pintype "passive"))
      (node (ref "U29") (pin "27") (pinfunction "VDD_27") (pintype "passive"))
      (node (ref "U29") (pin "28") (pinfunction "VDD_28") (pintype "passive"))
      (node (ref "U29") (pin "29") (pinfunction "VDD_29") (pintype "passive"))
      (node (ref "U29") (pin "3") (pinfunction "VDD_3") (pintype "passive"))
      (node (ref "U29") (pin "30") (pinfunction "VDD_30") (pintype "passive"))
      (node (ref "U29") (pin "31") (pinfunction "VDD_31") (pintype "passive"))
      (node (ref "U29") (pin "32") (pinfunction "VDD_32") (pintype "passive"))
      (node (ref "U29") (pin "33") (pinfunction "VDD_33") (pintype "passive"))
      (node (ref "U29") (pin "34") (pinfunction "VDD_34") (pintype "passive"))
      (node (ref "U29") (pin "35") (pinfunction "VDD_35") (pintype "passive"))
      (node (ref "U29") (pin "4") (pinfunction "VDD_4") (pintype "passive"))
      (node (ref "U29") (pin "5") (pinfunction "VDD_5") (pintype "passive"))
      (node (ref "U29") (pin "6") (pinfunction "VDD_6") (pintype "passive"))
      (node (ref "U29") (pin "7") (pinfunction "VDD_7") (pintype "passive"))
      (node (ref "U29") (pin "8") (pinfunction "VDD_8") (pintype "passive"))
      (node (ref "U29") (pin "9") (pinfunction "VDD_9") (pintype "passive"))
      (node (ref "U33") (pin "17") (pinfunction "VDD_17") (pintype "passive"))
    )
    (net (code "36") (name "/RX0_2") (class "Default")
      (node (ref "U33") (pin "12") (pinfunction "RX_0_12") (pintype "passive"))
    )
    (net (code "37") (name "/RX1_2") (class "Default")
      (node (ref "U33") (pin "14") (pinfunction "RX_1_14") (pintype "passive"))
    )
    (net (code "38") (name "/RX2_2") (class "Default")
      (node (ref "U33") (pin "16") (pinfunction "RX_2_16") (pintype "passive"))
    )
    (net (code "39") (name "/TX0_2") (class "Default")
      (node (ref "U33") (pin "11") (pinfunction "TX_0_11") (pintype "passive"))
    )
    (net (code "40") (name "/TX1_2") (class "Default")
      (node (ref "U33") (pin "13") (pinfunction "TX_1_13") (pintype "passive"))
    )
    (net (code "41") (name "/TX2_2") (class "Default")
      (node (ref "U33") (pin "15") (pinfunction "TX_2_15") (pintype "passive"))
    )
  )
)
